# Keyboard__Schematic.net
KiCad netlist of a schematic drawn in EAGLE
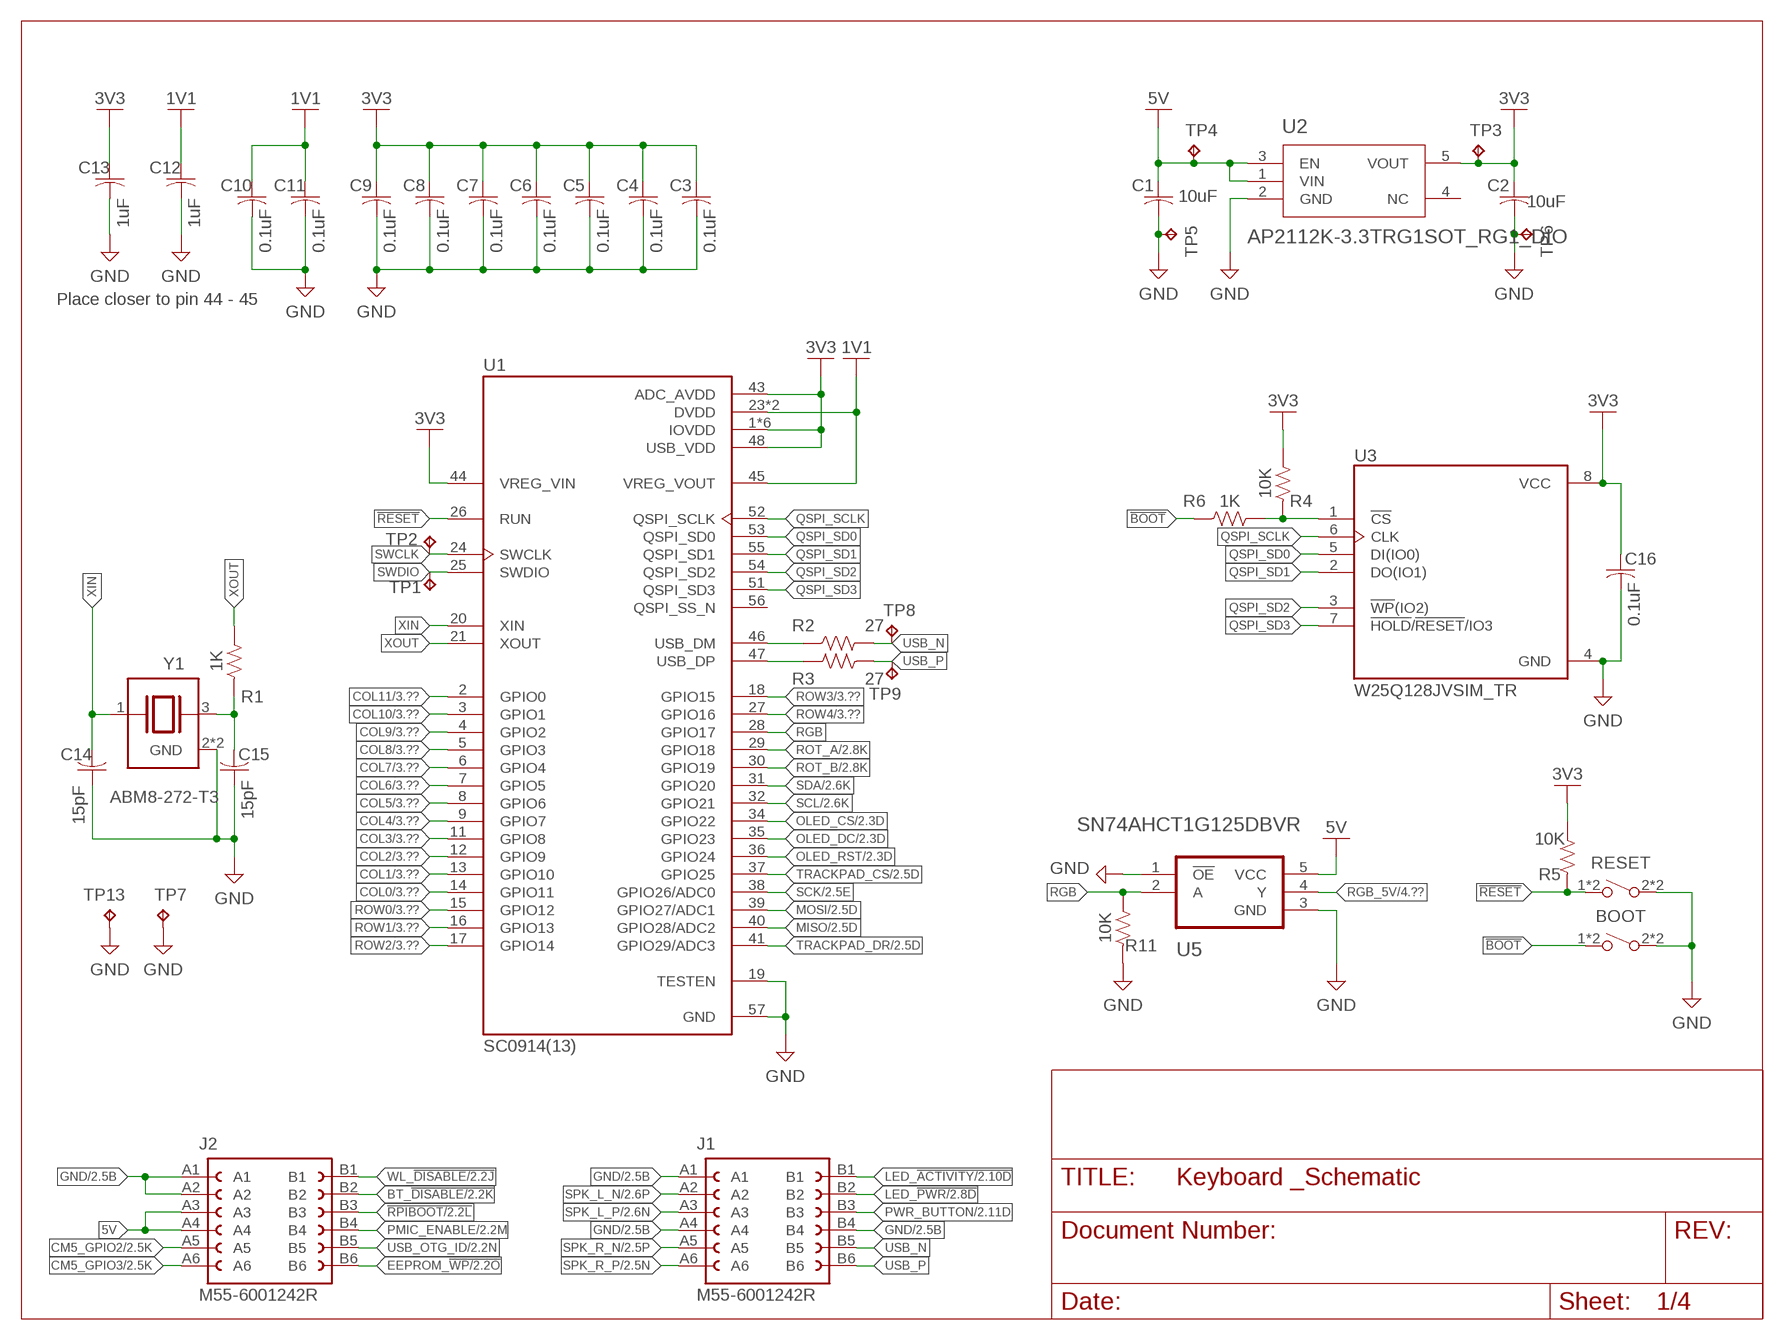
[diagram p0: schematic, sheet 1]
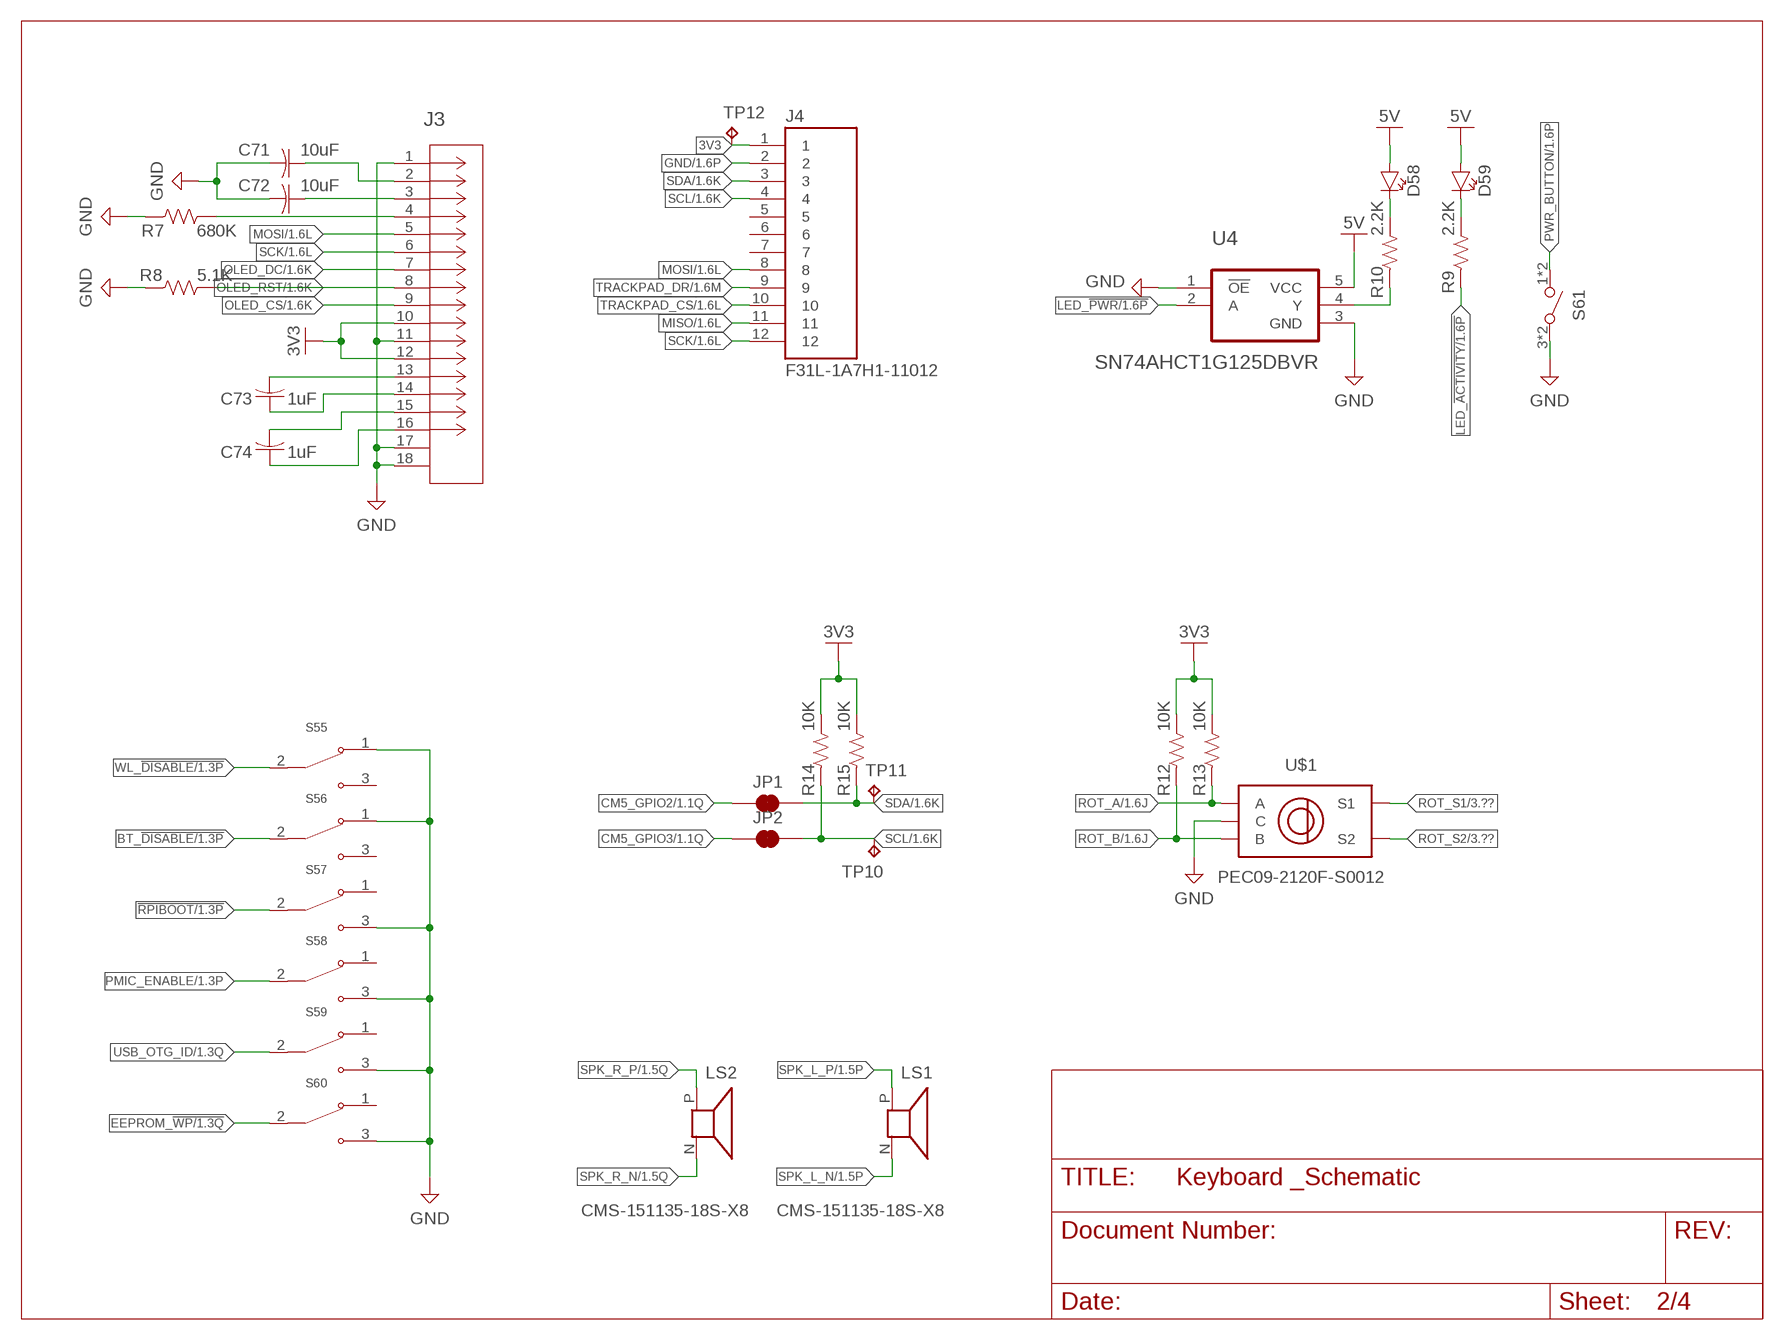
[diagram p1: schematic, sheet 2]
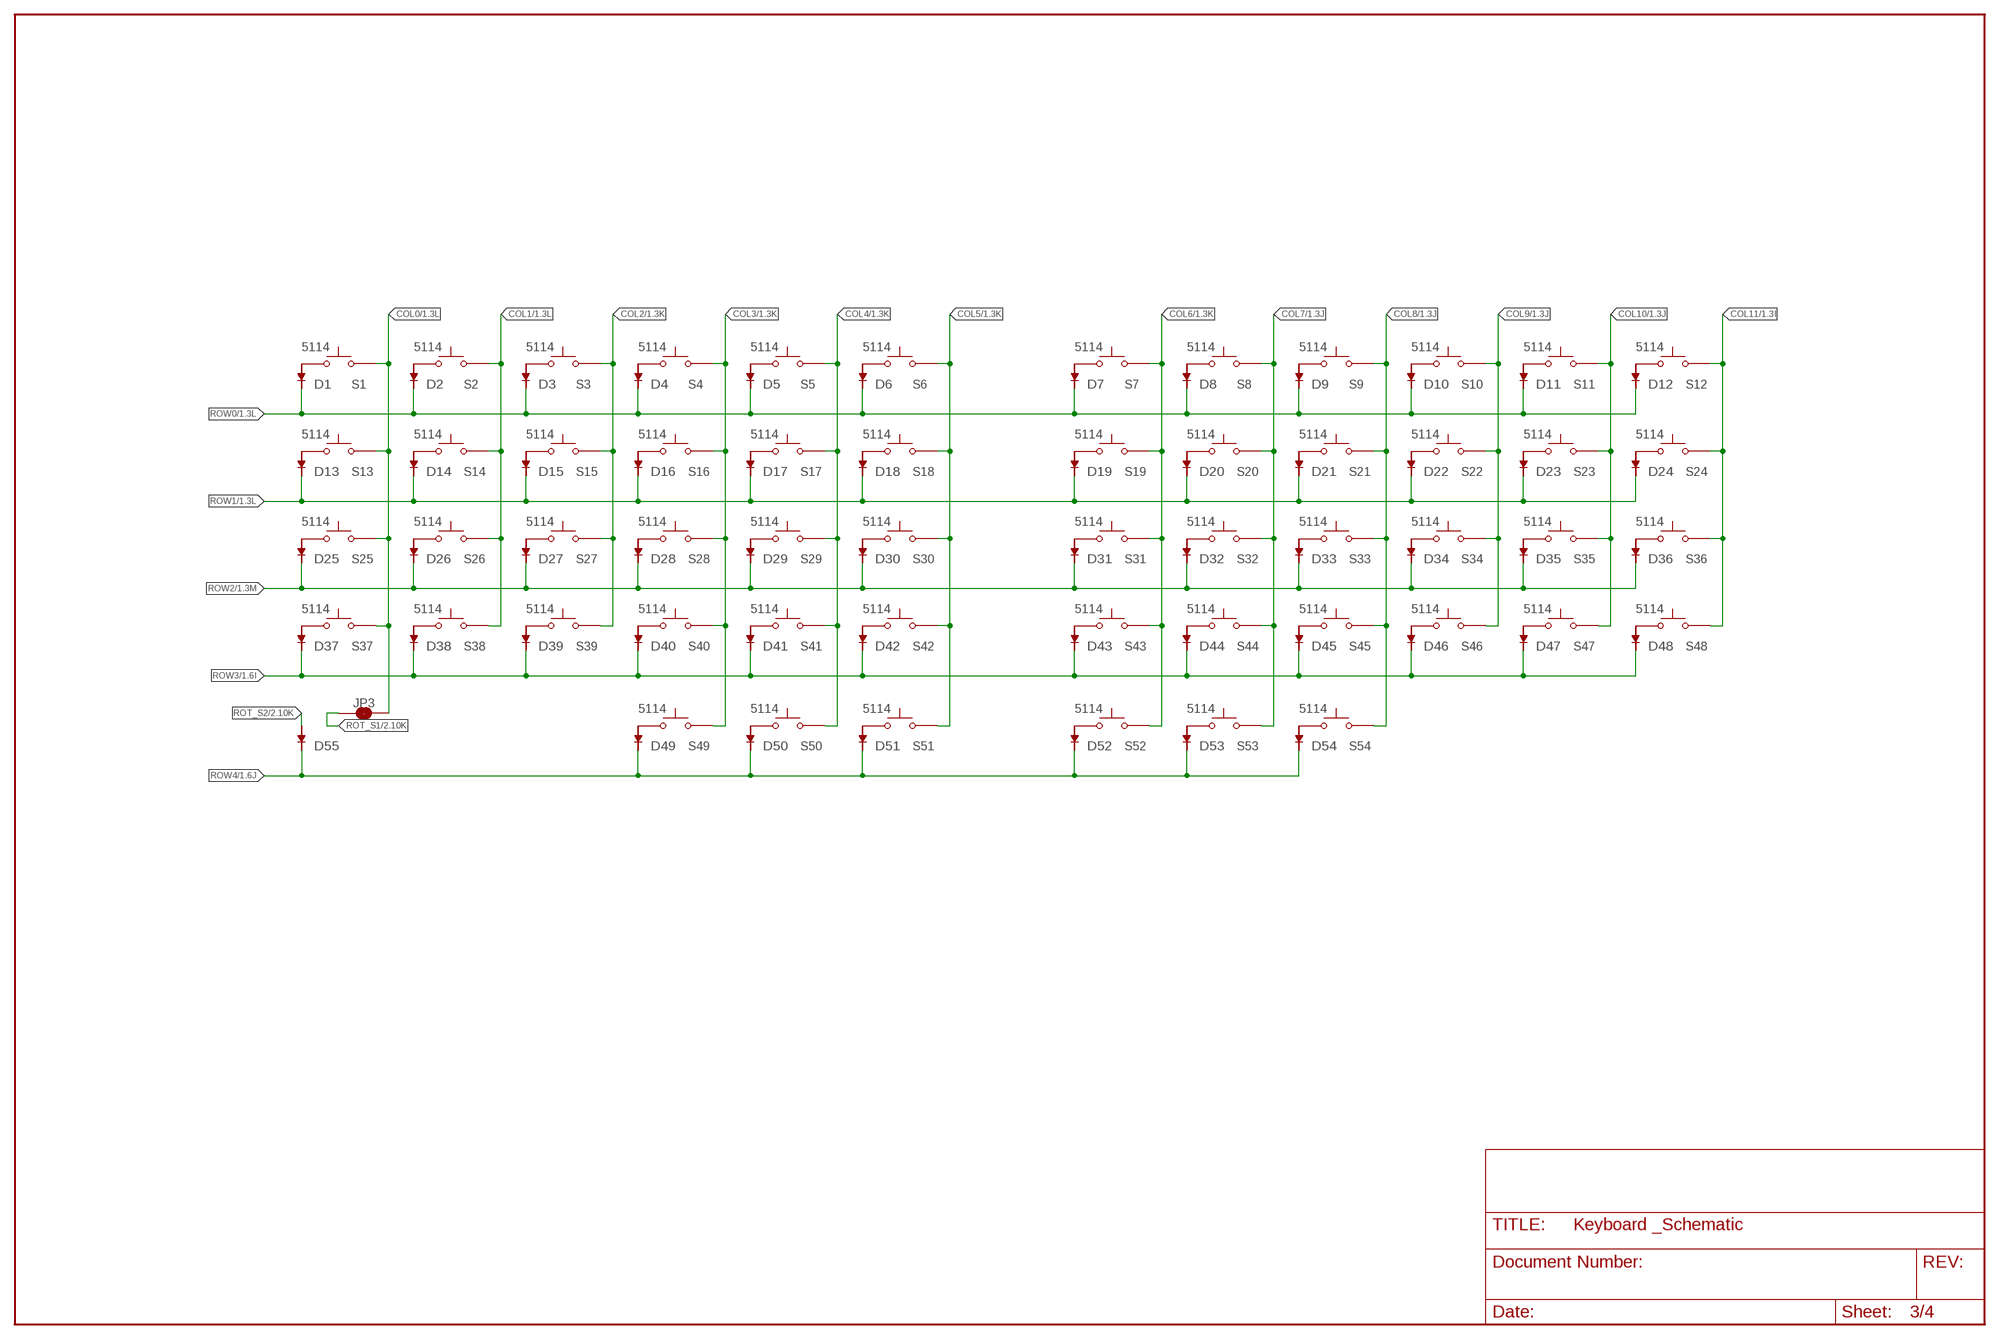
[diagram p2: schematic, sheet 3]
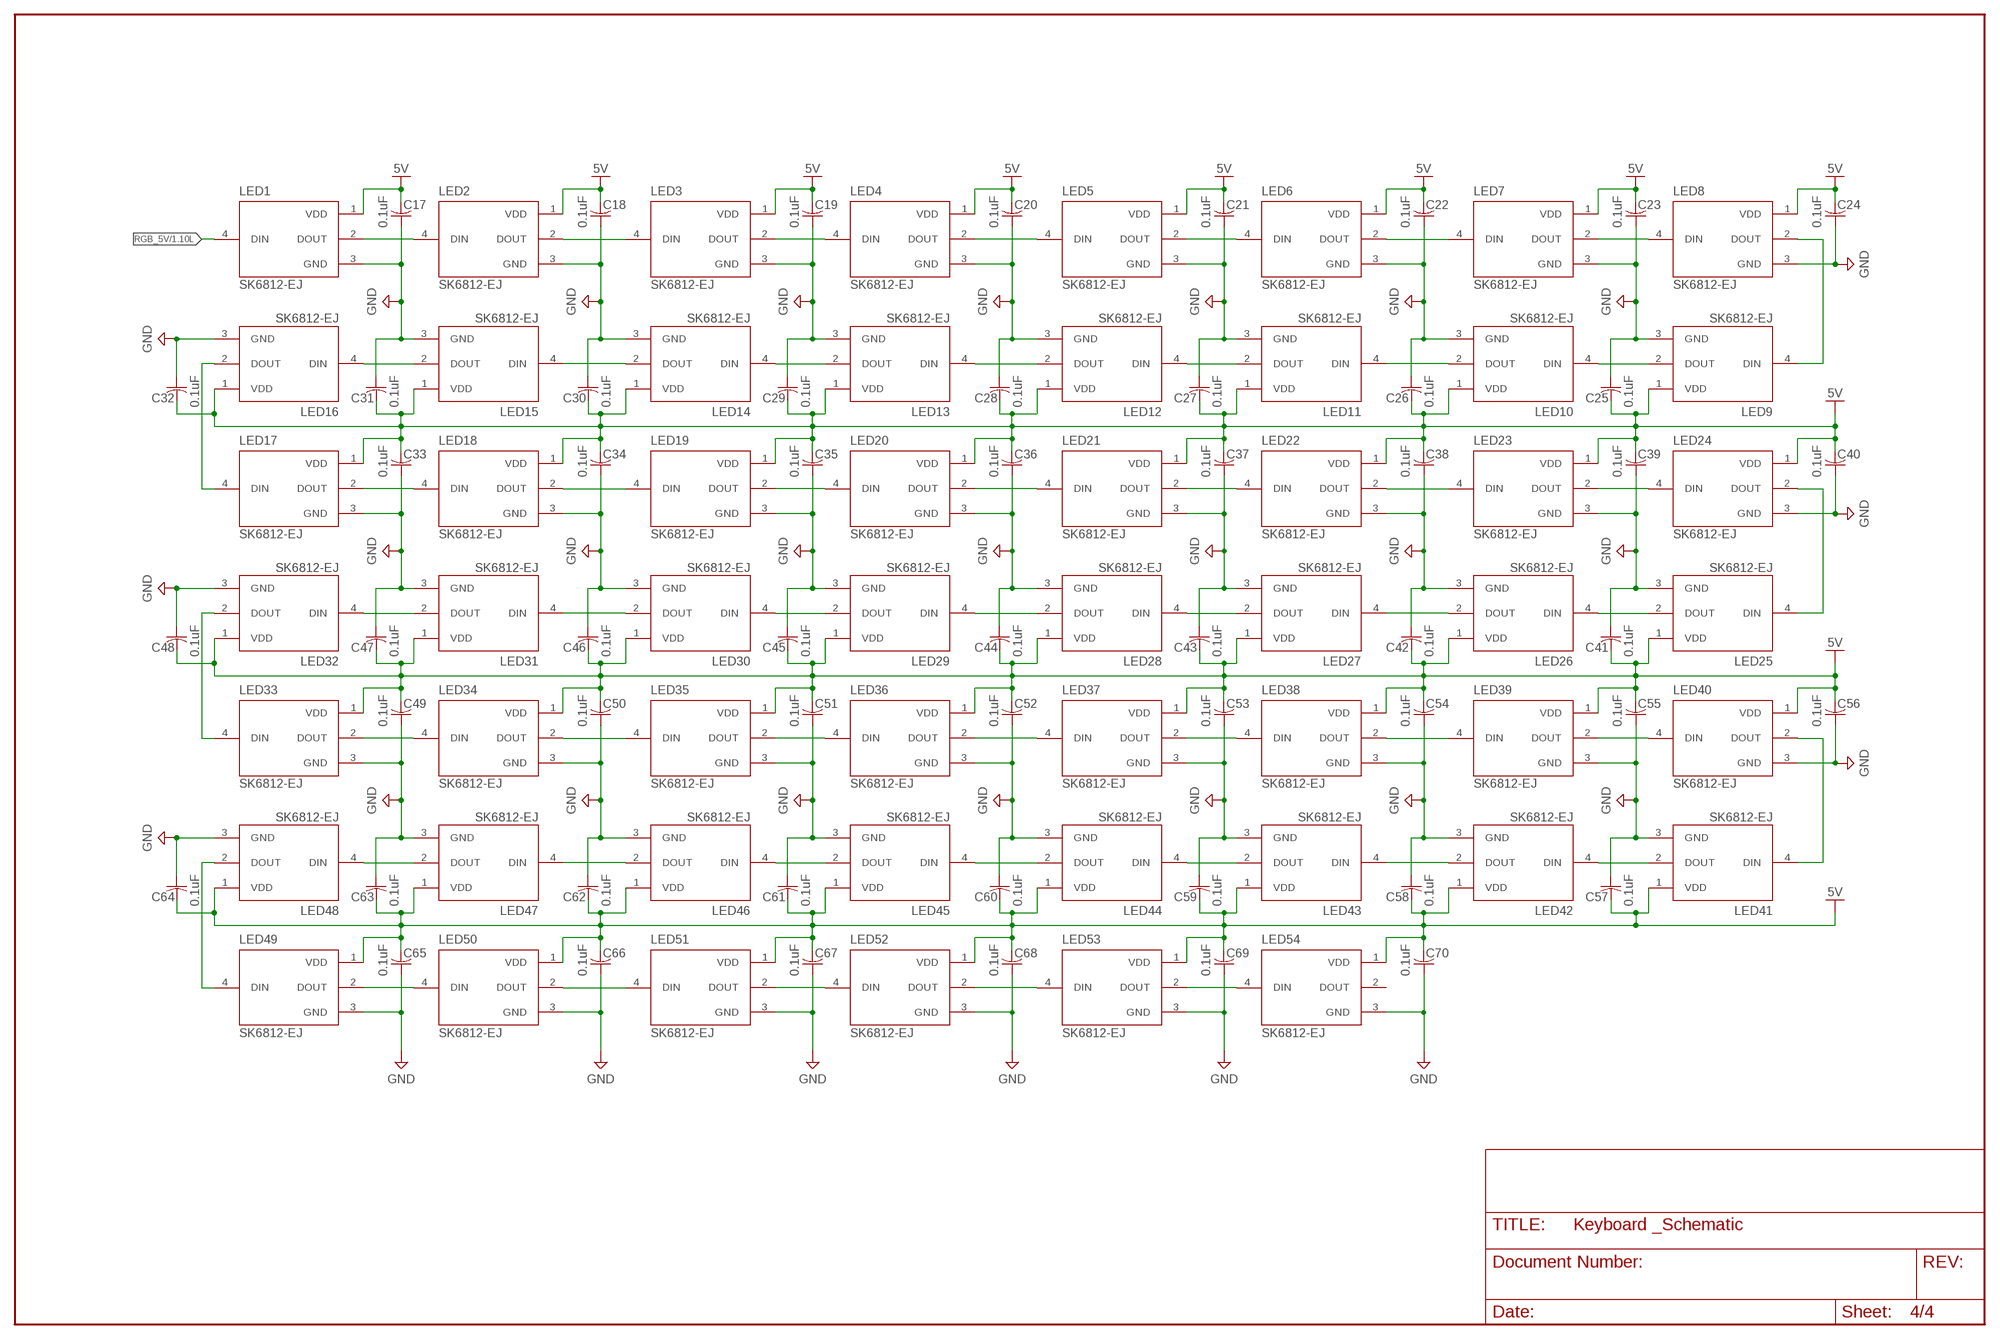
[diagram p3: schematic, sheet 4]

(export (version "E")
  (design (tool "Eeschema 10.0.6"))
  (components
    (comp (ref "BOOT")
      (value "SPST-NO_SWITCH_KMR2")
      (footprint "eagle-import:KMR2")
      (fields (field (name "MANUFACTURER") "C&K") (field (name "MPN") "KMR211G LFS"))
      (libsource (lib "eagle-import") (part "SPST-NO_SWITCH_KMR2"))
    )
    (comp (ref "C1")
      (value "10uF")
      (footprint "eagle-import:CAPC3216X135")
      (libsource (lib "eagle-import") (part "C-USCHIP-1206(3216-METRIC)_"))
    )
    (comp (ref "C2")
      (value "10uF")
      (footprint "eagle-import:CAPC3216X135")
      (libsource (lib "eagle-import") (part "C-USCHIP-1206(3216-METRIC)_"))
    )
    (comp (ref "C3")
      (value "0.1uF")
      (footprint "eagle-import:CAPC2012X110")
      (libsource (lib "eagle-import") (part "C-USCHIP-0805(2012-METRIC)_"))
    )
    (comp (ref "C4")
      (value "0.1uF")
      (footprint "eagle-import:CAPC2012X110")
      (libsource (lib "eagle-import") (part "C-USCHIP-0805(2012-METRIC)_"))
    )
    (comp (ref "C5")
      (value "0.1uF")
      (footprint "eagle-import:CAPC2012X110")
      (libsource (lib "eagle-import") (part "C-USCHIP-0805(2012-METRIC)_"))
    )
    (comp (ref "C6")
      (value "0.1uF")
      (footprint "eagle-import:CAPC2012X110")
      (libsource (lib "eagle-import") (part "C-USCHIP-0805(2012-METRIC)_"))
    )
    (comp (ref "C7")
      (value "0.1uF")
      (footprint "eagle-import:CAPC2012X110")
      (libsource (lib "eagle-import") (part "C-USCHIP-0805(2012-METRIC)_"))
    )
    (comp (ref "C8")
      (value "0.1uF")
      (footprint "eagle-import:CAPC2012X110")
      (libsource (lib "eagle-import") (part "C-USCHIP-0805(2012-METRIC)_"))
    )
    (comp (ref "C9")
      (value "0.1uF")
      (footprint "eagle-import:CAPC2012X110")
      (libsource (lib "eagle-import") (part "C-USCHIP-0805(2012-METRIC)_"))
    )
    (comp (ref "C10")
      (value "0.1uF")
      (footprint "eagle-import:CAPC2012X110")
      (libsource (lib "eagle-import") (part "C-USCHIP-0805(2012-METRIC)_"))
    )
    (comp (ref "C11")
      (value "0.1uF")
      (footprint "eagle-import:CAPC2012X110")
      (libsource (lib "eagle-import") (part "C-USCHIP-0805(2012-METRIC)_"))
    )
    (comp (ref "C12")
      (value "1uF")
      (footprint "eagle-import:CAPC2012X110")
      (libsource (lib "eagle-import") (part "C-USCHIP-0805(2012-METRIC)_"))
    )
    (comp (ref "C13")
      (value "1uF")
      (footprint "eagle-import:CAPC2012X110")
      (libsource (lib "eagle-import") (part "C-USCHIP-0805(2012-METRIC)_"))
    )
    (comp (ref "C14")
      (value "15pF")
      (footprint "eagle-import:CAPC2012X110")
      (libsource (lib "eagle-import") (part "C-USCHIP-0805(2012-METRIC)_"))
    )
    (comp (ref "C15")
      (value "15pF")
      (footprint "eagle-import:CAPC2012X110")
      (libsource (lib "eagle-import") (part "C-USCHIP-0805(2012-METRIC)_"))
    )
    (comp (ref "C16")
      (value "0.1uF")
      (footprint "eagle-import:CAPC2012X110")
      (libsource (lib "eagle-import") (part "C-USCHIP-0805(2012-METRIC)_"))
    )
    (comp (ref "J1")
      (value "M55-6001242R")
      (footprint "eagle-import:HARWIN_M55-6001242R")
      (fields (field (name "MANUFACTURER") "Harwin"))
      (libsource (lib "eagle-import") (part "M55-6001242R"))
    )
    (comp (ref "J2")
      (value "M55-6001242R")
      (footprint "eagle-import:HARWIN_M55-6001242R")
      (fields (field (name "MANUFACTURER") "Harwin"))
      (libsource (lib "eagle-import") (part "M55-6001242R"))
    )
    (comp (ref "R1")
      (value "1K")
      (footprint "eagle-import:RESC2012X65")
      (libsource (lib "eagle-import") (part "R-USCHIP-0805(2012-METRIC)_"))
    )
    (comp (ref "R2")
      (value "27")
      (footprint "eagle-import:RESC2012X65")
      (libsource (lib "eagle-import") (part "R-USCHIP-0805(2012-METRIC)_"))
    )
    (comp (ref "R3")
      (value "27")
      (footprint "eagle-import:RESC2012X65")
      (libsource (lib "eagle-import") (part "R-USCHIP-0805(2012-METRIC)_"))
    )
    (comp (ref "R4")
      (value "10K")
      (footprint "eagle-import:RESC2012X65")
      (libsource (lib "eagle-import") (part "R-USCHIP-0805(2012-METRIC)_"))
    )
    (comp (ref "R5")
      (value "10K")
      (footprint "eagle-import:RESC2012X65")
      (libsource (lib "eagle-import") (part "R-USCHIP-0805(2012-METRIC)_"))
    )
    (comp (ref "R6")
      (value "1K")
      (footprint "eagle-import:RESC2012X65")
      (libsource (lib "eagle-import") (part "R-USCHIP-0805(2012-METRIC)_"))
    )
    (comp (ref "R11")
      (value "10K")
      (footprint "eagle-import:RESC2012X65")
      (libsource (lib "eagle-import") (part "R-USCHIP-0805(2012-METRIC)_"))
    )
    (comp (ref "RESET")
      (value "SPST-NO_SWITCH_KMR2")
      (footprint "eagle-import:KMR2")
      (fields (field (name "MANUFACTURER") "C&K") (field (name "MPN") "KMR211G LFS"))
      (libsource (lib "eagle-import") (part "SPST-NO_SWITCH_KMR2"))
    )
    (comp (ref "TP1")
      (value "TPB2,54")
      (footprint "eagle-import:B2,54")
      (libsource (lib "eagle-import") (part "TPB2,54"))
    )
    (comp (ref "TP2")
      (value "TPB2,54")
      (footprint "eagle-import:B2,54")
      (libsource (lib "eagle-import") (part "TPB2,54"))
    )
    (comp (ref "TP3")
      (value "TPB2,54")
      (footprint "eagle-import:B2,54")
      (libsource (lib "eagle-import") (part "TPB2,54"))
    )
    (comp (ref "TP4")
      (value "TPB1,27")
      (footprint "eagle-import:B1,27")
      (libsource (lib "eagle-import") (part "TPB1,27"))
    )
    (comp (ref "TP5")
      (value "TPB2,54")
      (footprint "eagle-import:B2,54")
      (libsource (lib "eagle-import") (part "TPB2,54"))
    )
    (comp (ref "TP6")
      (value "TPB1,27")
      (footprint "eagle-import:B1,27")
      (libsource (lib "eagle-import") (part "TPB1,27"))
    )
    (comp (ref "TP7")
      (value "TPB1,27")
      (footprint "eagle-import:B1,27")
      (libsource (lib "eagle-import") (part "TPB1,27"))
    )
    (comp (ref "TP8")
      (value "TPB1,27")
      (footprint "eagle-import:B1,27")
      (libsource (lib "eagle-import") (part "TPB1,27"))
    )
    (comp (ref "TP9")
      (value "TPB1,27")
      (footprint "eagle-import:B1,27")
      (libsource (lib "eagle-import") (part "TPB1,27"))
    )
    (comp (ref "TP13")
      (value "TPB2,54")
      (footprint "eagle-import:B2,54")
      (libsource (lib "eagle-import") (part "TPB2,54"))
    )
    (comp (ref "U1")
      (value "SC0914(13)")
      (footprint "eagle-import:QFN40P700X700X90-57N")
      (fields (field (name "MANUFACTURER") "Raspberry Pi"))
      (libsource (lib "eagle-import") (part "SC0914(13)"))
    )
    (comp (ref "U2")
      (value "AP2112K-3.3TRG1SOT_RG1_DIO")
      (footprint "eagle-import:SOT_RG1_DIO")
      (fields
        (field (name "MANUFACTURER_PART_NUMBER") "AP2112K-3.3TRG1")
        (field (name "COPYRIGHT") "Copyright (C) 2025 Ultra Librarian. All rights reserved.")
      )
      (libsource (lib "eagle-import") (part "AP2112K-3.3TRG1SOT_RG1_DIO"))
    )
    (comp (ref "U3")
      (value "W25Q128JVSIM_TR")
      (footprint "eagle-import:SOIC127P790X216-8N")
      (fields (field (name "MF") "Winbond Electronics") (field (name "MP") "W25Q128JVSIM TR"))
      (libsource (lib "eagle-import") (part "W25Q128JVSIM_TR"))
    )
    (comp (ref "U5")
      (value "SN74AHCT1G125DBVR")
      (footprint "eagle-import:SOT95P280X145-5N")
      (libsource (lib "eagle-import") (part "SN74AHCT1G125DBVR"))
    )
    (comp (ref "Y1")
      (value "ABM8-272-T3")
      (footprint "eagle-import:XTAL_ABM8-272-T3")
      (fields (field (name "MANUFACTURER") "ABRACON") (field (name "CREATOR") "DIZAR"))
      (libsource (lib "eagle-import") (part "ABM8-272-T3"))
    )
    (comp (ref "D1")
      (value "1N4148W")
      (footprint "eagle-import:SOD3715X135N")
      (fields (field (name "MF") "Diodes Inc.") (field (name "MP") "1N4148W-7-F"))
      (libsource (lib "eagle-import") (part "1N4148W"))
    )
    (comp (ref "D2")
      (value "1N4148W")
      (footprint "eagle-import:SOD3715X135N")
      (fields (field (name "MF") "Diodes Inc.") (field (name "MP") "1N4148W-7-F"))
      (libsource (lib "eagle-import") (part "1N4148W"))
    )
    (comp (ref "D3")
      (value "1N4148W")
      (footprint "eagle-import:SOD3715X135N")
      (fields (field (name "MF") "Diodes Inc.") (field (name "MP") "1N4148W-7-F"))
      (libsource (lib "eagle-import") (part "1N4148W"))
    )
    (comp (ref "D4")
      (value "1N4148W")
      (footprint "eagle-import:SOD3715X135N")
      (fields (field (name "MF") "Diodes Inc.") (field (name "MP") "1N4148W-7-F"))
      (libsource (lib "eagle-import") (part "1N4148W"))
    )
    (comp (ref "D5")
      (value "1N4148W")
      (footprint "eagle-import:SOD3715X135N")
      (fields (field (name "MF") "Diodes Inc.") (field (name "MP") "1N4148W-7-F"))
      (libsource (lib "eagle-import") (part "1N4148W"))
    )
    (comp (ref "D6")
      (value "1N4148W")
      (footprint "eagle-import:SOD3715X135N")
      (fields (field (name "MF") "Diodes Inc.") (field (name "MP") "1N4148W-7-F"))
      (libsource (lib "eagle-import") (part "1N4148W"))
    )
    (comp (ref "D7")
      (value "1N4148W")
      (footprint "eagle-import:SOD3715X135N")
      (fields (field (name "MF") "Diodes Inc.") (field (name "MP") "1N4148W-7-F"))
      (libsource (lib "eagle-import") (part "1N4148W"))
    )
    (comp (ref "D8")
      (value "1N4148W")
      (footprint "eagle-import:SOD3715X135N")
      (fields (field (name "MF") "Diodes Inc.") (field (name "MP") "1N4148W-7-F"))
      (libsource (lib "eagle-import") (part "1N4148W"))
    )
    (comp (ref "D9")
      (value "1N4148W")
      (footprint "eagle-import:SOD3715X135N")
      (fields (field (name "MF") "Diodes Inc.") (field (name "MP") "1N4148W-7-F"))
      (libsource (lib "eagle-import") (part "1N4148W"))
    )
    (comp (ref "D10")
      (value "1N4148W")
      (footprint "eagle-import:SOD3715X135N")
      (fields (field (name "MF") "Diodes Inc.") (field (name "MP") "1N4148W-7-F"))
      (libsource (lib "eagle-import") (part "1N4148W"))
    )
    (comp (ref "D11")
      (value "1N4148W")
      (footprint "eagle-import:SOD3715X135N")
      (fields (field (name "MF") "Diodes Inc.") (field (name "MP") "1N4148W-7-F"))
      (libsource (lib "eagle-import") (part "1N4148W"))
    )
    (comp (ref "D12")
      (value "1N4148W")
      (footprint "eagle-import:SOD3715X135N")
      (fields (field (name "MF") "Diodes Inc.") (field (name "MP") "1N4148W-7-F"))
      (libsource (lib "eagle-import") (part "1N4148W"))
    )
    (comp (ref "D13")
      (value "1N4148W")
      (footprint "eagle-import:SOD3715X135N")
      (fields (field (name "MF") "Diodes Inc.") (field (name "MP") "1N4148W-7-F"))
      (libsource (lib "eagle-import") (part "1N4148W"))
    )
    (comp (ref "D14")
      (value "1N4148W")
      (footprint "eagle-import:SOD3715X135N")
      (fields (field (name "MF") "Diodes Inc.") (field (name "MP") "1N4148W-7-F"))
      (libsource (lib "eagle-import") (part "1N4148W"))
    )
    (comp (ref "D15")
      (value "1N4148W")
      (footprint "eagle-import:SOD3715X135N")
      (fields (field (name "MF") "Diodes Inc.") (field (name "MP") "1N4148W-7-F"))
      (libsource (lib "eagle-import") (part "1N4148W"))
    )
    (comp (ref "D16")
      (value "1N4148W")
      (footprint "eagle-import:SOD3715X135N")
      (fields (field (name "MF") "Diodes Inc.") (field (name "MP") "1N4148W-7-F"))
      (libsource (lib "eagle-import") (part "1N4148W"))
    )
    (comp (ref "D17")
      (value "1N4148W")
      (footprint "eagle-import:SOD3715X135N")
      (fields (field (name "MF") "Diodes Inc.") (field (name "MP") "1N4148W-7-F"))
      (libsource (lib "eagle-import") (part "1N4148W"))
    )
    (comp (ref "D18")
      (value "1N4148W")
      (footprint "eagle-import:SOD3715X135N")
      (fields (field (name "MF") "Diodes Inc.") (field (name "MP") "1N4148W-7-F"))
      (libsource (lib "eagle-import") (part "1N4148W"))
    )
    (comp (ref "D19")
      (value "1N4148W")
      (footprint "eagle-import:SOD3715X135N")
      (fields (field (name "MF") "Diodes Inc.") (field (name "MP") "1N4148W-7-F"))
      (libsource (lib "eagle-import") (part "1N4148W"))
    )
    (comp (ref "D20")
      (value "1N4148W")
      (footprint "eagle-import:SOD3715X135N")
      (fields (field (name "MF") "Diodes Inc.") (field (name "MP") "1N4148W-7-F"))
      (libsource (lib "eagle-import") (part "1N4148W"))
    )
    (comp (ref "D21")
      (value "1N4148W")
      (footprint "eagle-import:SOD3715X135N")
      (fields (field (name "MF") "Diodes Inc.") (field (name "MP") "1N4148W-7-F"))
      (libsource (lib "eagle-import") (part "1N4148W"))
    )
    (comp (ref "D22")
      (value "1N4148W")
      (footprint "eagle-import:SOD3715X135N")
      (fields (field (name "MF") "Diodes Inc.") (field (name "MP") "1N4148W-7-F"))
      (libsource (lib "eagle-import") (part "1N4148W"))
    )
    (comp (ref "D23")
      (value "1N4148W")
      (footprint "eagle-import:SOD3715X135N")
      (fields (field (name "MF") "Diodes Inc.") (field (name "MP") "1N4148W-7-F"))
      (libsource (lib "eagle-import") (part "1N4148W"))
    )
    (comp (ref "D24")
      (value "1N4148W")
      (footprint "eagle-import:SOD3715X135N")
      (fields (field (name "MF") "Diodes Inc.") (field (name "MP") "1N4148W-7-F"))
      (libsource (lib "eagle-import") (part "1N4148W"))
    )
    (comp (ref "D25")
      (value "1N4148W")
      (footprint "eagle-import:SOD3715X135N")
      (fields (field (name "MF") "Diodes Inc.") (field (name "MP") "1N4148W-7-F"))
      (libsource (lib "eagle-import") (part "1N4148W"))
    )
    (comp (ref "D26")
      (value "1N4148W")
      (footprint "eagle-import:SOD3715X135N")
      (fields (field (name "MF") "Diodes Inc.") (field (name "MP") "1N4148W-7-F"))
      (libsource (lib "eagle-import") (part "1N4148W"))
    )
    (comp (ref "D27")
      (value "1N4148W")
      (footprint "eagle-import:SOD3715X135N")
      (fields (field (name "MF") "Diodes Inc.") (field (name "MP") "1N4148W-7-F"))
      (libsource (lib "eagle-import") (part "1N4148W"))
    )
    (comp (ref "D28")
      (value "1N4148W")
      (footprint "eagle-import:SOD3715X135N")
      (fields (field (name "MF") "Diodes Inc.") (field (name "MP") "1N4148W-7-F"))
      (libsource (lib "eagle-import") (part "1N4148W"))
    )
    (comp (ref "D29")
      (value "1N4148W")
      (footprint "eagle-import:SOD3715X135N")
      (fields (field (name "MF") "Diodes Inc.") (field (name "MP") "1N4148W-7-F"))
      (libsource (lib "eagle-import") (part "1N4148W"))
    )
    (comp (ref "D30")
      (value "1N4148W")
      (footprint "eagle-import:SOD3715X135N")
      (fields (field (name "MF") "Diodes Inc.") (field (name "MP") "1N4148W-7-F"))
      (libsource (lib "eagle-import") (part "1N4148W"))
    )
    (comp (ref "D31")
      (value "1N4148W")
      (footprint "eagle-import:SOD3715X135N")
      (fields (field (name "MF") "Diodes Inc.") (field (name "MP") "1N4148W-7-F"))
      (libsource (lib "eagle-import") (part "1N4148W"))
    )
    (comp (ref "D32")
      (value "1N4148W")
      (footprint "eagle-import:SOD3715X135N")
      (fields (field (name "MF") "Diodes Inc.") (field (name "MP") "1N4148W-7-F"))
      (libsource (lib "eagle-import") (part "1N4148W"))
    )
    (comp (ref "D33")
      (value "1N4148W")
      (footprint "eagle-import:SOD3715X135N")
      (fields (field (name "MF") "Diodes Inc.") (field (name "MP") "1N4148W-7-F"))
      (libsource (lib "eagle-import") (part "1N4148W"))
    )
    (comp (ref "D34")
      (value "1N4148W")
      (footprint "eagle-import:SOD3715X135N")
      (fields (field (name "MF") "Diodes Inc.") (field (name "MP") "1N4148W-7-F"))
      (libsource (lib "eagle-import") (part "1N4148W"))
    )
    (comp (ref "D35")
      (value "1N4148W")
      (footprint "eagle-import:SOD3715X135N")
      (fields (field (name "MF") "Diodes Inc.") (field (name "MP") "1N4148W-7-F"))
      (libsource (lib "eagle-import") (part "1N4148W"))
    )
    (comp (ref "D36")
      (value "1N4148W")
      (footprint "eagle-import:SOD3715X135N")
      (fields (field (name "MF") "Diodes Inc.") (field (name "MP") "1N4148W-7-F"))
      (libsource (lib "eagle-import") (part "1N4148W"))
    )
    (comp (ref "D37")
      (value "1N4148W")
      (footprint "eagle-import:SOD3715X135N")
      (fields (field (name "MF") "Diodes Inc.") (field (name "MP") "1N4148W-7-F"))
      (libsource (lib "eagle-import") (part "1N4148W"))
    )
    (comp (ref "D38")
      (value "1N4148W")
      (footprint "eagle-import:SOD3715X135N")
      (fields (field (name "MF") "Diodes Inc.") (field (name "MP") "1N4148W-7-F"))
      (libsource (lib "eagle-import") (part "1N4148W"))
    )
    (comp (ref "D39")
      (value "1N4148W")
      (footprint "eagle-import:SOD3715X135N")
      (fields (field (name "MF") "Diodes Inc.") (field (name "MP") "1N4148W-7-F"))
      (libsource (lib "eagle-import") (part "1N4148W"))
    )
    (comp (ref "D40")
      (value "1N4148W")
      (footprint "eagle-import:SOD3715X135N")
      (fields (field (name "MF") "Diodes Inc.") (field (name "MP") "1N4148W-7-F"))
      (libsource (lib "eagle-import") (part "1N4148W"))
    )
    (comp (ref "D41")
      (value "1N4148W")
      (footprint "eagle-import:SOD3715X135N")
      (fields (field (name "MF") "Diodes Inc.") (field (name "MP") "1N4148W-7-F"))
      (libsource (lib "eagle-import") (part "1N4148W"))
    )
    (comp (ref "D42")
      (value "1N4148W")
      (footprint "eagle-import:SOD3715X135N")
      (fields (field (name "MF") "Diodes Inc.") (field (name "MP") "1N4148W-7-F"))
      (libsource (lib "eagle-import") (part "1N4148W"))
    )
    (comp (ref "D43")
      (value "1N4148W")
      (footprint "eagle-import:SOD3715X135N")
      (fields (field (name "MF") "Diodes Inc.") (field (name "MP") "1N4148W-7-F"))
      (libsource (lib "eagle-import") (part "1N4148W"))
    )
    (comp (ref "D44")
      (value "1N4148W")
      (footprint "eagle-import:SOD3715X135N")
      (fields (field (name "MF") "Diodes Inc.") (field (name "MP") "1N4148W-7-F"))
      (libsource (lib "eagle-import") (part "1N4148W"))
    )
    (comp (ref "D45")
      (value "1N4148W")
      (footprint "eagle-import:SOD3715X135N")
      (fields (field (name "MF") "Diodes Inc.") (field (name "MP") "1N4148W-7-F"))
      (libsource (lib "eagle-import") (part "1N4148W"))
    )
    (comp (ref "D46")
      (value "1N4148W")
      (footprint "eagle-import:SOD3715X135N")
      (fields (field (name "MF") "Diodes Inc.") (field (name "MP") "1N4148W-7-F"))
      (libsource (lib "eagle-import") (part "1N4148W"))
    )
    (comp (ref "D47")
      (value "1N4148W")
      (footprint "eagle-import:SOD3715X135N")
      (fields (field (name "MF") "Diodes Inc.") (field (name "MP") "1N4148W-7-F"))
      (libsource (lib "eagle-import") (part "1N4148W"))
    )
    (comp (ref "D48")
      (value "1N4148W")
      (footprint "eagle-import:SOD3715X135N")
      (fields (field (name "MF") "Diodes Inc.") (field (name "MP") "1N4148W-7-F"))
      (libsource (lib "eagle-import") (part "1N4148W"))
    )
    (comp (ref "D49")
      (value "1N4148W")
      (footprint "eagle-import:SOD3715X135N")
      (fields (field (name "MF") "Diodes Inc.") (field (name "MP") "1N4148W-7-F"))
      (libsource (lib "eagle-import") (part "1N4148W"))
    )
    (comp (ref "D50")
      (value "1N4148W")
      (footprint "eagle-import:SOD3715X135N")
      (fields (field (name "MF") "Diodes Inc.") (field (name "MP") "1N4148W-7-F"))
      (libsource (lib "eagle-import") (part "1N4148W"))
    )
    (comp (ref "D51")
      (value "1N4148W")
      (footprint "eagle-import:SOD3715X135N")
      (fields (field (name "MF") "Diodes Inc.") (field (name "MP") "1N4148W-7-F"))
      (libsource (lib "eagle-import") (part "1N4148W"))
    )
    (comp (ref "D52")
      (value "1N4148W")
      (footprint "eagle-import:SOD3715X135N")
      (fields (field (name "MF") "Diodes Inc.") (field (name "MP") "1N4148W-7-F"))
      (libsource (lib "eagle-import") (part "1N4148W"))
    )
    (comp (ref "D53")
      (value "1N4148W")
      (footprint "eagle-import:SOD3715X135N")
      (fields (field (name "MF") "Diodes Inc.") (field (name "MP") "1N4148W-7-F"))
      (libsource (lib "eagle-import") (part "1N4148W"))
    )
    (comp (ref "D54")
      (value "1N4148W")
      (footprint "eagle-import:SOD3715X135N")
      (fields (field (name "MF") "Diodes Inc.") (field (name "MP") "1N4148W-7-F"))
      (libsource (lib "eagle-import") (part "1N4148W"))
    )
    (comp (ref "D55")
      (value "1N4148W")
      (footprint "eagle-import:SOD3715X135N")
      (fields (field (name "MF") "Diodes Inc.") (field (name "MP") "1N4148W-7-F"))
      (libsource (lib "eagle-import") (part "1N4148W"))
    )
    (comp (ref "JP3")
      (value "JUMPER-SMT_2_NC_TRACE_NO-SILK")
      (footprint "eagle-import:SMT-JUMPER_2_NC_TRACE_NO-SILK")
      (libsource (lib "eagle-import") (part "JUMPER-SMT_2_NC_TRACE_NO-SILK"))
    )
    (comp (ref "S1")
      (value "5114")
      (footprint "eagle-import:SW_5114")
      (fields (field (name "MF") "Adafruit Industries LLC"))
      (libsource (lib "eagle-import") (part "5114"))
    )
    (comp (ref "S2")
      (value "5114")
      (footprint "eagle-import:SW_5114")
      (fields (field (name "MF") "Adafruit Industries LLC"))
      (libsource (lib "eagle-import") (part "5114"))
    )
    (comp (ref "S3")
      (value "5114")
      (footprint "eagle-import:SW_5114")
      (fields (field (name "MF") "Adafruit Industries LLC"))
      (libsource (lib "eagle-import") (part "5114"))
    )
    (comp (ref "S4")
      (value "5114")
      (footprint "eagle-import:SW_5114")
      (fields (field (name "MF") "Adafruit Industries LLC"))
      (libsource (lib "eagle-import") (part "5114"))
    )
    (comp (ref "S5")
      (value "5114")
      (footprint "eagle-import:SW_5114")
      (fields (field (name "MF") "Adafruit Industries LLC"))
      (libsource (lib "eagle-import") (part "5114"))
    )
    (comp (ref "S6")
      (value "5114")
      (footprint "eagle-import:SW_5114")
      (fields (field (name "MF") "Adafruit Industries LLC"))
      (libsource (lib "eagle-import") (part "5114"))
    )
    (comp (ref "S7")
      (value "5114")
      (footprint "eagle-import:SW_5114")
      (fields (field (name "MF") "Adafruit Industries LLC"))
      (libsource (lib "eagle-import") (part "5114"))
    )
    (comp (ref "S8")
      (value "5114")
      (footprint "eagle-import:SW_5114")
      (fields (field (name "MF") "Adafruit Industries LLC"))
      (libsource (lib "eagle-import") (part "5114"))
    )
    (comp (ref "S9")
      (value "5114")
      (footprint "eagle-import:SW_5114")
      (fields (field (name "MF") "Adafruit Industries LLC"))
      (libsource (lib "eagle-import") (part "5114"))
    )
    (comp (ref "S10")
      (value "5114")
      (footprint "eagle-import:SW_5114")
      (fields (field (name "MF") "Adafruit Industries LLC"))
      (libsource (lib "eagle-import") (part "5114"))
    )
    (comp (ref "S11")
      (value "5114")
      (footprint "eagle-import:SW_5114")
      (fields (field (name "MF") "Adafruit Industries LLC"))
      (libsource (lib "eagle-import") (part "5114"))
    )
    (comp (ref "S12")
      (value "5114")
      (footprint "eagle-import:SW_5114")
      (fields (field (name "MF") "Adafruit Industries LLC"))
      (libsource (lib "eagle-import") (part "5114"))
    )
    (comp (ref "S13")
      (value "5114")
      (footprint "eagle-import:SW_5114")
      (fields (field (name "MF") "Adafruit Industries LLC"))
      (libsource (lib "eagle-import") (part "5114"))
    )
    (comp (ref "S14")
      (value "5114")
      (footprint "eagle-import:SW_5114")
      (fields (field (name "MF") "Adafruit Industries LLC"))
      (libsource (lib "eagle-import") (part "5114"))
    )
    (comp (ref "S15")
      (value "5114")
      (footprint "eagle-import:SW_5114")
      (fields (field (name "MF") "Adafruit Industries LLC"))
      (libsource (lib "eagle-import") (part "5114"))
    )
    (comp (ref "S16")
      (value "5114")
      (footprint "eagle-import:SW_5114")
      (fields (field (name "MF") "Adafruit Industries LLC"))
      (libsource (lib "eagle-import") (part "5114"))
    )
    (comp (ref "S17")
      (value "5114")
      (footprint "eagle-import:SW_5114")
      (fields (field (name "MF") "Adafruit Industries LLC"))
      (libsource (lib "eagle-import") (part "5114"))
    )
    (comp (ref "S18")
      (value "5114")
      (footprint "eagle-import:SW_5114")
      (fields (field (name "MF") "Adafruit Industries LLC"))
      (libsource (lib "eagle-import") (part "5114"))
    )
    (comp (ref "S19")
      (value "5114")
      (footprint "eagle-import:SW_5114")
      (fields (field (name "MF") "Adafruit Industries LLC"))
      (libsource (lib "eagle-import") (part "5114"))
    )
    (comp (ref "S20")
      (value "5114")
      (footprint "eagle-import:SW_5114")
      (fields (field (name "MF") "Adafruit Industries LLC"))
      (libsource (lib "eagle-import") (part "5114"))
    )
    (comp (ref "S21")
      (value "5114")
      (footprint "eagle-import:SW_5114")
      (fields (field (name "MF") "Adafruit Industries LLC"))
      (libsource (lib "eagle-import") (part "5114"))
    )
    (comp (ref "S22")
      (value "5114")
      (footprint "eagle-import:SW_5114")
      (fields (field (name "MF") "Adafruit Industries LLC"))
      (libsource (lib "eagle-import") (part "5114"))
    )
    (comp (ref "S23")
      (value "5114")
      (footprint "eagle-import:SW_5114")
      (fields (field (name "MF") "Adafruit Industries LLC"))
      (libsource (lib "eagle-import") (part "5114"))
    )
    (comp (ref "S24")
      (value "5114")
      (footprint "eagle-import:SW_5114")
      (fields (field (name "MF") "Adafruit Industries LLC"))
      (libsource (lib "eagle-import") (part "5114"))
    )
    (comp (ref "S25")
      (value "5114")
      (footprint "eagle-import:SW_5114")
      (fields (field (name "MF") "Adafruit Industries LLC"))
      (libsource (lib "eagle-import") (part "5114"))
    )
    (comp (ref "S26")
      (value "5114")
      (footprint "eagle-import:SW_5114")
      (fields (field (name "MF") "Adafruit Industries LLC"))
      (libsource (lib "eagle-import") (part "5114"))
    )
    (comp (ref "S27")
      (value "5114")
      (footprint "eagle-import:SW_5114")
      (fields (field (name "MF") "Adafruit Industries LLC"))
      (libsource (lib "eagle-import") (part "5114"))
    )
    (comp (ref "S28")
      (value "5114")
      (footprint "eagle-import:SW_5114")
      (fields (field (name "MF") "Adafruit Industries LLC"))
      (libsource (lib "eagle-import") (part "5114"))
    )
    (comp (ref "S29")
      (value "5114")
      (footprint "eagle-import:SW_5114")
      (fields (field (name "MF") "Adafruit Industries LLC"))
      (libsource (lib "eagle-import") (part "5114"))
    )
    (comp (ref "S30")
      (value "5114")
      (footprint "eagle-import:SW_5114")
      (fields (field (name "MF") "Adafruit Industries LLC"))
      (libsource (lib "eagle-import") (part "5114"))
    )
    (comp (ref "S31")
      (value "5114")
      (footprint "eagle-import:SW_5114")
      (fields (field (name "MF") "Adafruit Industries LLC"))
      (libsource (lib "eagle-import") (part "5114"))
    )
    (comp (ref "S32")
      (value "5114")
      (footprint "eagle-import:SW_5114")
      (fields (field (name "MF") "Adafruit Industries LLC"))
      (libsource (lib "eagle-import") (part "5114"))
    )
    (comp (ref "S33")
      (value "5114")
      (footprint "eagle-import:SW_5114")
      (fields (field (name "MF") "Adafruit Industries LLC"))
      (libsource (lib "eagle-import") (part "5114"))
    )
    (comp (ref "S34")
      (value "5114")
      (footprint "eagle-import:SW_5114")
      (fields (field (name "MF") "Adafruit Industries LLC"))
      (libsource (lib "eagle-import") (part "5114"))
    )
    (comp (ref "S35")
      (value "5114")
      (footprint "eagle-import:SW_5114")
      (fields (field (name "MF") "Adafruit Industries LLC"))
      (libsource (lib "eagle-import") (part "5114"))
    )
    (comp (ref "S36")
      (value "5114")
      (footprint "eagle-import:SW_5114")
      (fields (field (name "MF") "Adafruit Industries LLC"))
      (libsource (lib "eagle-import") (part "5114"))
    )
    (comp (ref "S37")
      (value "5114")
      (footprint "eagle-import:SW_5114")
      (fields (field (name "MF") "Adafruit Industries LLC"))
      (libsource (lib "eagle-import") (part "5114"))
    )
    (comp (ref "S38")
      (value "5114")
      (footprint "eagle-import:SW_5114")
      (fields (field (name "MF") "Adafruit Industries LLC"))
      (libsource (lib "eagle-import") (part "5114"))
    )
    (comp (ref "S39")
      (value "5114")
      (footprint "eagle-import:SW_5114")
      (fields (field (name "MF") "Adafruit Industries LLC"))
      (libsource (lib "eagle-import") (part "5114"))
    )
    (comp (ref "S40")
      (value "5114")
      (footprint "eagle-import:SW_5114")
      (fields (field (name "MF") "Adafruit Industries LLC"))
      (libsource (lib "eagle-import") (part "5114"))
    )
    (comp (ref "S41")
      (value "5114")
      (footprint "eagle-import:SW_5114")
      (fields (field (name "MF") "Adafruit Industries LLC"))
      (libsource (lib "eagle-import") (part "5114"))
    )
    (comp (ref "S42")
      (value "5114")
      (footprint "eagle-import:SW_5114")
      (fields (field (name "MF") "Adafruit Industries LLC"))
      (libsource (lib "eagle-import") (part "5114"))
    )
    (comp (ref "S43")
      (value "5114")
      (footprint "eagle-import:SW_5114")
      (fields (field (name "MF") "Adafruit Industries LLC"))
      (libsource (lib "eagle-import") (part "5114"))
    )
    (comp (ref "S44")
      (value "5114")
      (footprint "eagle-import:SW_5114")
      (fields (field (name "MF") "Adafruit Industries LLC"))
      (libsource (lib "eagle-import") (part "5114"))
    )
    (comp (ref "S45")
      (value "5114")
      (footprint "eagle-import:SW_5114")
      (fields (field (name "MF") "Adafruit Industries LLC"))
      (libsource (lib "eagle-import") (part "5114"))
    )
    (comp (ref "S46")
      (value "5114")
      (footprint "eagle-import:SW_5114")
      (fields (field (name "MF") "Adafruit Industries LLC"))
      (libsource (lib "eagle-import") (part "5114"))
    )
    (comp (ref "S47")
      (value "5114")
      (footprint "eagle-import:SW_5114")
      (fields (field (name "MF") "Adafruit Industries LLC"))
      (libsource (lib "eagle-import") (part "5114"))
    )
    (comp (ref "S48")
      (value "5114")
      (footprint "eagle-import:SW_5114")
      (fields (field (name "MF") "Adafruit Industries LLC"))
      (libsource (lib "eagle-import") (part "5114"))
    )
    (comp (ref "S49")
      (value "5114")
      (footprint "eagle-import:SW_5114")
      (fields (field (name "MF") "Adafruit Industries LLC"))
      (libsource (lib "eagle-import") (part "5114"))
    )
    (comp (ref "S50")
      (value "5114")
      (footprint "eagle-import:SW_5114")
      (fields (field (name "MF") "Adafruit Industries LLC"))
      (libsource (lib "eagle-import") (part "5114"))
    )
    (comp (ref "S51")
      (value "5114")
      (footprint "eagle-import:SW_5114")
      (fields (field (name "MF") "Adafruit Industries LLC"))
      (libsource (lib "eagle-import") (part "5114"))
    )
    (comp (ref "S52")
      (value "5114")
      (footprint "eagle-import:SW_5114")
      (fields (field (name "MF") "Adafruit Industries LLC"))
      (libsource (lib "eagle-import") (part "5114"))
    )
    (comp (ref "S53")
      (value "5114")
      (footprint "eagle-import:SW_5114")
      (fields (field (name "MF") "Adafruit Industries LLC"))
      (libsource (lib "eagle-import") (part "5114"))
    )
    (comp (ref "S54")
      (value "5114")
      (footprint "eagle-import:SW_5114")
      (fields (field (name "MF") "Adafruit Industries LLC"))
      (libsource (lib "eagle-import") (part "5114"))
    )
    (comp (ref "C71")
      (value "10uF")
      (footprint "eagle-import:CAPC3216X135")
      (libsource (lib "eagle-import") (part "C-USCHIP-1206(3216-METRIC)_"))
    )
    (comp (ref "C72")
      (value "10uF")
      (footprint "eagle-import:CAPC3216X135")
      (libsource (lib "eagle-import") (part "C-USCHIP-1206(3216-METRIC)_"))
    )
    (comp (ref "C73")
      (value "1uF")
      (footprint "eagle-import:CAPC2012X110")
      (libsource (lib "eagle-import") (part "C-USCHIP-0805(2012-METRIC)_"))
    )
    (comp (ref "C74")
      (value "1uF")
      (footprint "eagle-import:CAPC2012X110")
      (libsource (lib "eagle-import") (part "C-USCHIP-0805(2012-METRIC)_"))
    )
    (comp (ref "D58")
      (value "CHIP-FLAT-G_1206")
      (footprint "eagle-import:LEDC3216X75N_FLAT-G")
      (libsource (lib "eagle-import") (part "CHIP-FLAT-G_1206"))
    )
    (comp (ref "D59")
      (value "CHIP-FLAT-G_1206")
      (footprint "eagle-import:LEDC3216X75N_FLAT-G")
      (libsource (lib "eagle-import") (part "CHIP-FLAT-G_1206"))
    )
    (comp (ref "J3")
      (value "1-1775333-6CONN16_1-1775333-6_TEC")
      (footprint "eagle-import:CONN16_1-1775333-6_TEC")
      (fields
        (field (name "MANUFACTURER_PART_NUMBER") "1-1775333-6")
        (field (name "COPYRIGHT") "Copyright (C) 2025 Ultra Librarian. All rights reserved.")
      )
      (libsource (lib "eagle-import") (part "1-1775333-6CONN16_1-1775333-6_TEC"))
    )
    (comp (ref "J4")
      (value "F31L-1A7H1-11012")
      (footprint "eagle-import:AMPHENOL_F31L-1A7H1-11012")
      (fields (field (name "MANUFACTURER") "Amphenol ICC"))
      (libsource (lib "eagle-import") (part "F31L-1A7H1-11012"))
    )
    (comp (ref "JP1")
      (value "JUMPER-SMT_2_NC_TRACE_NO-SILK")
      (footprint "eagle-import:SMT-JUMPER_2_NC_TRACE_NO-SILK")
      (libsource (lib "eagle-import") (part "JUMPER-SMT_2_NC_TRACE_NO-SILK"))
    )
    (comp (ref "JP2")
      (value "JUMPER-SMT_2_NC_TRACE_NO-SILK")
      (footprint "eagle-import:SMT-JUMPER_2_NC_TRACE_NO-SILK")
      (libsource (lib "eagle-import") (part "JUMPER-SMT_2_NC_TRACE_NO-SILK"))
    )
    (comp (ref "LS1")
      (value "CMS-151135-18S-X8")
      (footprint "eagle-import:SPKR_CMS-151135-18S-X8")
      (fields (field (name "MANUFACTURER") "CUI Devices"))
      (libsource (lib "eagle-import") (part "CMS-151135-18S-X8"))
    )
    (comp (ref "LS2")
      (value "CMS-151135-18S-X8")
      (footprint "eagle-import:SPKR_CMS-151135-18S-X8")
      (fields (field (name "MANUFACTURER") "CUI Devices"))
      (libsource (lib "eagle-import") (part "CMS-151135-18S-X8"))
    )
    (comp (ref "R7")
      (value "680K")
      (footprint "eagle-import:RESC2012X65")
      (libsource (lib "eagle-import") (part "R-USCHIP-0805(2012-METRIC)_"))
    )
    (comp (ref "R8")
      (value "5.1K")
      (footprint "eagle-import:RESC2012X65")
      (libsource (lib "eagle-import") (part "R-USCHIP-0805(2012-METRIC)_"))
    )
    (comp (ref "R9")
      (value "2.2K")
      (footprint "eagle-import:RESC2012X65")
      (libsource (lib "eagle-import") (part "R-USCHIP-0805(2012-METRIC)_"))
    )
    (comp (ref "R10")
      (value "2.2K")
      (footprint "eagle-import:RESC2012X65")
      (libsource (lib "eagle-import") (part "R-USCHIP-0805(2012-METRIC)_"))
    )
    (comp (ref "R12")
      (value "10K")
      (footprint "eagle-import:RESC2012X65")
      (libsource (lib "eagle-import") (part "R-USCHIP-0805(2012-METRIC)_"))
    )
    (comp (ref "R13")
      (value "10K")
      (footprint "eagle-import:RESC2012X65")
      (libsource (lib "eagle-import") (part "R-USCHIP-0805(2012-METRIC)_"))
    )
    (comp (ref "R14")
      (value "10K")
      (footprint "eagle-import:RESC2012X65")
      (libsource (lib "eagle-import") (part "R-USCHIP-0805(2012-METRIC)_"))
    )
    (comp (ref "R15")
      (value "10K")
      (footprint "eagle-import:RESC2012X65")
      (libsource (lib "eagle-import") (part "R-USCHIP-0805(2012-METRIC)_"))
    )
    (comp (ref "S55")
      (value "SLW-1277744-3A-N-D")
      (footprint "eagle-import:SW_SLW-1277744-3A-N-D")
      (fields (field (name "MANUFACTURER") "Same Sky"))
      (libsource (lib "eagle-import") (part "SLW-1277744-3A-N-D"))
    )
    (comp (ref "S56")
      (value "SLW-1277744-3A-N-D")
      (footprint "eagle-import:SW_SLW-1277744-3A-N-D")
      (fields (field (name "MANUFACTURER") "Same Sky"))
      (libsource (lib "eagle-import") (part "SLW-1277744-3A-N-D"))
    )
    (comp (ref "S57")
      (value "SLW-1277744-3A-N-D")
      (footprint "eagle-import:SW_SLW-1277744-3A-N-D")
      (fields (field (name "MANUFACTURER") "Same Sky"))
      (libsource (lib "eagle-import") (part "SLW-1277744-3A-N-D"))
    )
    (comp (ref "S58")
      (value "SLW-1277744-3A-N-D")
      (footprint "eagle-import:SW_SLW-1277744-3A-N-D")
      (fields (field (name "MANUFACTURER") "Same Sky"))
      (libsource (lib "eagle-import") (part "SLW-1277744-3A-N-D"))
    )
    (comp (ref "S59")
      (value "SLW-1277744-3A-N-D")
      (footprint "eagle-import:SW_SLW-1277744-3A-N-D")
      (fields (field (name "MANUFACTURER") "Same Sky"))
      (libsource (lib "eagle-import") (part "SLW-1277744-3A-N-D"))
    )
    (comp (ref "S60")
      (value "SLW-1277744-3A-N-D")
      (footprint "eagle-import:SW_SLW-1277744-3A-N-D")
      (fields (field (name "MANUFACTURER") "Same Sky"))
      (libsource (lib "eagle-import") (part "SLW-1277744-3A-N-D"))
    )
    (comp (ref "S61")
      (value "SPST-NO_SWITCH_PTS645-SMT-6MM")
      (footprint "eagle-import:PTS645-SMT-6MM")
      (fields (field (name "MANUFACTURER") "C&K") (field (name "MPN") "PTS645SM43SMTR92 LFS"))
      (libsource (lib "eagle-import") (part "SPST-NO_SWITCH_PTS645-SMT-6MM"))
    )
    (comp (ref "TP10")
      (value "TPB1,27")
      (footprint "eagle-import:B1,27")
      (libsource (lib "eagle-import") (part "TPB1,27"))
    )
    (comp (ref "TP11")
      (value "TPB1,27")
      (footprint "eagle-import:B1,27")
      (libsource (lib "eagle-import") (part "TPB1,27"))
    )
    (comp (ref "TP12")
      (value "TPB1,27")
      (footprint "eagle-import:B1,27")
      (libsource (lib "eagle-import") (part "TPB1,27"))
    )
    (comp (ref "U$1")
      (value "PEC09-2120F-S0012")
      (footprint "eagle-import:PEC09-2XXXF-SXXXX")
      (libsource (lib "eagle-import") (part "PEC09-2120F-S0012"))
    )
    (comp (ref "U4")
      (value "SN74AHCT1G125DBVR")
      (footprint "eagle-import:SOT95P280X145-5N")
      (libsource (lib "eagle-import") (part "SN74AHCT1G125DBVR"))
    )
    (comp (ref "C17")
      (value "0.1uF")
      (footprint "eagle-import:CAPC2012X110")
      (libsource (lib "eagle-import") (part "C-USCHIP-0805(2012-METRIC)_"))
    )
    (comp (ref "C18")
      (value "0.1uF")
      (footprint "eagle-import:CAPC2012X110")
      (libsource (lib "eagle-import") (part "C-USCHIP-0805(2012-METRIC)_"))
    )
    (comp (ref "C19")
      (value "0.1uF")
      (footprint "eagle-import:CAPC2012X110")
      (libsource (lib "eagle-import") (part "C-USCHIP-0805(2012-METRIC)_"))
    )
    (comp (ref "C20")
      (value "0.1uF")
      (footprint "eagle-import:CAPC2012X110")
      (libsource (lib "eagle-import") (part "C-USCHIP-0805(2012-METRIC)_"))
    )
    (comp (ref "C21")
      (value "0.1uF")
      (footprint "eagle-import:CAPC2012X110")
      (libsource (lib "eagle-import") (part "C-USCHIP-0805(2012-METRIC)_"))
    )
    (comp (ref "C22")
      (value "0.1uF")
      (footprint "eagle-import:CAPC2012X110")
      (libsource (lib "eagle-import") (part "C-USCHIP-0805(2012-METRIC)_"))
    )
    (comp (ref "C23")
      (value "0.1uF")
      (footprint "eagle-import:CAPC2012X110")
      (libsource (lib "eagle-import") (part "C-USCHIP-0805(2012-METRIC)_"))
    )
    (comp (ref "C24")
      (value "0.1uF")
      (footprint "eagle-import:CAPC2012X110")
      (libsource (lib "eagle-import") (part "C-USCHIP-0805(2012-METRIC)_"))
    )
    (comp (ref "C25")
      (value "0.1uF")
      (footprint "eagle-import:CAPC2012X110")
      (libsource (lib "eagle-import") (part "C-USCHIP-0805(2012-METRIC)_"))
    )
    (comp (ref "C26")
      (value "0.1uF")
      (footprint "eagle-import:CAPC2012X110")
      (libsource (lib "eagle-import") (part "C-USCHIP-0805(2012-METRIC)_"))
    )
    (comp (ref "C27")
      (value "0.1uF")
      (footprint "eagle-import:CAPC2012X110")
      (libsource (lib "eagle-import") (part "C-USCHIP-0805(2012-METRIC)_"))
    )
    (comp (ref "C28")
      (value "0.1uF")
      (footprint "eagle-import:CAPC2012X110")
      (libsource (lib "eagle-import") (part "C-USCHIP-0805(2012-METRIC)_"))
    )
    (comp (ref "C29")
      (value "0.1uF")
      (footprint "eagle-import:CAPC2012X110")
      (libsource (lib "eagle-import") (part "C-USCHIP-0805(2012-METRIC)_"))
    )
    (comp (ref "C30")
      (value "0.1uF")
      (footprint "eagle-import:CAPC2012X110")
      (libsource (lib "eagle-import") (part "C-USCHIP-0805(2012-METRIC)_"))
    )
    (comp (ref "C31")
      (value "0.1uF")
      (footprint "eagle-import:CAPC2012X110")
      (libsource (lib "eagle-import") (part "C-USCHIP-0805(2012-METRIC)_"))
    )
    (comp (ref "C32")
      (value "0.1uF")
      (footprint "eagle-import:CAPC2012X110")
      (libsource (lib "eagle-import") (part "C-USCHIP-0805(2012-METRIC)_"))
    )
    (comp (ref "C33")
      (value "0.1uF")
      (footprint "eagle-import:CAPC2012X110")
      (libsource (lib "eagle-import") (part "C-USCHIP-0805(2012-METRIC)_"))
    )
    (comp (ref "C34")
      (value "0.1uF")
      (footprint "eagle-import:CAPC2012X110")
      (libsource (lib "eagle-import") (part "C-USCHIP-0805(2012-METRIC)_"))
    )
    (comp (ref "C35")
      (value "0.1uF")
      (footprint "eagle-import:CAPC2012X110")
      (libsource (lib "eagle-import") (part "C-USCHIP-0805(2012-METRIC)_"))
    )
    (comp (ref "C36")
      (value "0.1uF")
      (footprint "eagle-import:CAPC2012X110")
      (libsource (lib "eagle-import") (part "C-USCHIP-0805(2012-METRIC)_"))
    )
    (comp (ref "C37")
      (value "0.1uF")
      (footprint "eagle-import:CAPC2012X110")
      (libsource (lib "eagle-import") (part "C-USCHIP-0805(2012-METRIC)_"))
    )
    (comp (ref "C38")
      (value "0.1uF")
      (footprint "eagle-import:CAPC2012X110")
      (libsource (lib "eagle-import") (part "C-USCHIP-0805(2012-METRIC)_"))
    )
    (comp (ref "C39")
      (value "0.1uF")
      (footprint "eagle-import:CAPC2012X110")
      (libsource (lib "eagle-import") (part "C-USCHIP-0805(2012-METRIC)_"))
    )
    (comp (ref "C40")
      (value "0.1uF")
      (footprint "eagle-import:CAPC2012X110")
      (libsource (lib "eagle-import") (part "C-USCHIP-0805(2012-METRIC)_"))
    )
    (comp (ref "C41")
      (value "0.1uF")
      (footprint "eagle-import:CAPC2012X110")
      (libsource (lib "eagle-import") (part "C-USCHIP-0805(2012-METRIC)_"))
    )
    (comp (ref "C42")
      (value "0.1uF")
      (footprint "eagle-import:CAPC2012X110")
      (libsource (lib "eagle-import") (part "C-USCHIP-0805(2012-METRIC)_"))
    )
    (comp (ref "C43")
      (value "0.1uF")
      (footprint "eagle-import:CAPC2012X110")
      (libsource (lib "eagle-import") (part "C-USCHIP-0805(2012-METRIC)_"))
    )
    (comp (ref "C44")
      (value "0.1uF")
      (footprint "eagle-import:CAPC2012X110")
      (libsource (lib "eagle-import") (part "C-USCHIP-0805(2012-METRIC)_"))
    )
    (comp (ref "C45")
      (value "0.1uF")
      (footprint "eagle-import:CAPC2012X110")
      (libsource (lib "eagle-import") (part "C-USCHIP-0805(2012-METRIC)_"))
    )
    (comp (ref "C46")
      (value "0.1uF")
      (footprint "eagle-import:CAPC2012X110")
      (libsource (lib "eagle-import") (part "C-USCHIP-0805(2012-METRIC)_"))
    )
    (comp (ref "C47")
      (value "0.1uF")
      (footprint "eagle-import:CAPC2012X110")
      (libsource (lib "eagle-import") (part "C-USCHIP-0805(2012-METRIC)_"))
    )
    (comp (ref "C48")
      (value "0.1uF")
      (footprint "eagle-import:CAPC2012X110")
      (libsource (lib "eagle-import") (part "C-USCHIP-0805(2012-METRIC)_"))
    )
    (comp (ref "C49")
      (value "0.1uF")
      (footprint "eagle-import:CAPC2012X110")
      (libsource (lib "eagle-import") (part "C-USCHIP-0805(2012-METRIC)_"))
    )
    (comp (ref "C50")
      (value "0.1uF")
      (footprint "eagle-import:CAPC2012X110")
      (libsource (lib "eagle-import") (part "C-USCHIP-0805(2012-METRIC)_"))
    )
    (comp (ref "C51")
      (value "0.1uF")
      (footprint "eagle-import:CAPC2012X110")
      (libsource (lib "eagle-import") (part "C-USCHIP-0805(2012-METRIC)_"))
    )
    (comp (ref "C52")
      (value "0.1uF")
      (footprint "eagle-import:CAPC2012X110")
      (libsource (lib "eagle-import") (part "C-USCHIP-0805(2012-METRIC)_"))
    )
    (comp (ref "C53")
      (value "0.1uF")
      (footprint "eagle-import:CAPC2012X110")
      (libsource (lib "eagle-import") (part "C-USCHIP-0805(2012-METRIC)_"))
    )
    (comp (ref "C54")
      (value "0.1uF")
      (footprint "eagle-import:CAPC2012X110")
      (libsource (lib "eagle-import") (part "C-USCHIP-0805(2012-METRIC)_"))
    )
    (comp (ref "C55")
      (value "0.1uF")
      (footprint "eagle-import:CAPC2012X110")
      (libsource (lib "eagle-import") (part "C-USCHIP-0805(2012-METRIC)_"))
    )
    (comp (ref "C56")
      (value "0.1uF")
      (footprint "eagle-import:CAPC2012X110")
      (libsource (lib "eagle-import") (part "C-USCHIP-0805(2012-METRIC)_"))
    )
    (comp (ref "C57")
      (value "0.1uF")
      (footprint "eagle-import:CAPC2012X110")
      (libsource (lib "eagle-import") (part "C-USCHIP-0805(2012-METRIC)_"))
    )
    (comp (ref "C58")
      (value "0.1uF")
      (footprint "eagle-import:CAPC2012X110")
      (libsource (lib "eagle-import") (part "C-USCHIP-0805(2012-METRIC)_"))
    )
    (comp (ref "C59")
      (value "0.1uF")
      (footprint "eagle-import:CAPC2012X110")
      (libsource (lib "eagle-import") (part "C-USCHIP-0805(2012-METRIC)_"))
    )
    (comp (ref "C60")
      (value "0.1uF")
      (footprint "eagle-import:CAPC2012X110")
      (libsource (lib "eagle-import") (part "C-USCHIP-0805(2012-METRIC)_"))
    )
    (comp (ref "C61")
      (value "0.1uF")
      (footprint "eagle-import:CAPC2012X110")
      (libsource (lib "eagle-import") (part "C-USCHIP-0805(2012-METRIC)_"))
    )
    (comp (ref "C62")
      (value "0.1uF")
      (footprint "eagle-import:CAPC2012X110")
      (libsource (lib "eagle-import") (part "C-USCHIP-0805(2012-METRIC)_"))
    )
    (comp (ref "C63")
      (value "0.1uF")
      (footprint "eagle-import:CAPC2012X110")
      (libsource (lib "eagle-import") (part "C-USCHIP-0805(2012-METRIC)_"))
    )
    (comp (ref "C64")
      (value "0.1uF")
      (footprint "eagle-import:CAPC2012X110")
      (libsource (lib "eagle-import") (part "C-USCHIP-0805(2012-METRIC)_"))
    )
    (comp (ref "C65")
      (value "0.1uF")
      (footprint "eagle-import:CAPC2012X110")
      (libsource (lib "eagle-import") (part "C-USCHIP-0805(2012-METRIC)_"))
    )
    (comp (ref "C66")
      (value "0.1uF")
      (footprint "eagle-import:CAPC2012X110")
      (libsource (lib "eagle-import") (part "C-USCHIP-0805(2012-METRIC)_"))
    )
    (comp (ref "C67")
      (value "0.1uF")
      (footprint "eagle-import:CAPC2012X110")
      (libsource (lib "eagle-import") (part "C-USCHIP-0805(2012-METRIC)_"))
    )
    (comp (ref "C68")
      (value "0.1uF")
      (footprint "eagle-import:CAPC2012X110")
      (libsource (lib "eagle-import") (part "C-USCHIP-0805(2012-METRIC)_"))
    )
    (comp (ref "C69")
      (value "0.1uF")
      (footprint "eagle-import:CAPC2012X110")
      (libsource (lib "eagle-import") (part "C-USCHIP-0805(2012-METRIC)_"))
    )
    (comp (ref "C70")
      (value "0.1uF")
      (footprint "eagle-import:CAPC2012X110")
      (libsource (lib "eagle-import") (part "C-USCHIP-0805(2012-METRIC)_"))
    )
    (comp (ref "LED1")
      (value "SK6812-EJ")
      (footprint "eagle-import:LED_SK6812-E")
      (fields (field (name "MF") "DONGGUANG OPSCO OPTOELECTRONICS CO., LTD") (field (name "MP") "SK6812-E"))
      (libsource (lib "eagle-import") (part "SK6812-EJ"))
    )
    (comp (ref "LED2")
      (value "SK6812-EJ")
      (footprint "eagle-import:LED_SK6812-E")
      (fields (field (name "MF") "DONGGUANG OPSCO OPTOELECTRONICS CO., LTD") (field (name "MP") "SK6812-E"))
      (libsource (lib "eagle-import") (part "SK6812-EJ"))
    )
    (comp (ref "LED3")
      (value "SK6812-EJ")
      (footprint "eagle-import:LED_SK6812-E")
      (fields (field (name "MF") "DONGGUANG OPSCO OPTOELECTRONICS CO., LTD") (field (name "MP") "SK6812-E"))
      (libsource (lib "eagle-import") (part "SK6812-EJ"))
    )
    (comp (ref "LED4")
      (value "SK6812-EJ")
      (footprint "eagle-import:LED_SK6812-E")
      (fields (field (name "MF") "DONGGUANG OPSCO OPTOELECTRONICS CO., LTD") (field (name "MP") "SK6812-E"))
      (libsource (lib "eagle-import") (part "SK6812-EJ"))
    )
    (comp (ref "LED5")
      (value "SK6812-EJ")
      (footprint "eagle-import:LED_SK6812-E")
      (fields (field (name "MF") "DONGGUANG OPSCO OPTOELECTRONICS CO., LTD") (field (name "MP") "SK6812-E"))
      (libsource (lib "eagle-import") (part "SK6812-EJ"))
    )
    (comp (ref "LED6")
      (value "SK6812-EJ")
      (footprint "eagle-import:LED_SK6812-E")
      (fields (field (name "MF") "DONGGUANG OPSCO OPTOELECTRONICS CO., LTD") (field (name "MP") "SK6812-E"))
      (libsource (lib "eagle-import") (part "SK6812-EJ"))
    )
    (comp (ref "LED7")
      (value "SK6812-EJ")
      (footprint "eagle-import:LED_SK6812-E")
      (fields (field (name "MF") "DONGGUANG OPSCO OPTOELECTRONICS CO., LTD") (field (name "MP") "SK6812-E"))
      (libsource (lib "eagle-import") (part "SK6812-EJ"))
    )
    (comp (ref "LED8")
      (value "SK6812-EJ")
      (footprint "eagle-import:LED_SK6812-E")
      (fields (field (name "MF") "DONGGUANG OPSCO OPTOELECTRONICS CO., LTD") (field (name "MP") "SK6812-E"))
      (libsource (lib "eagle-import") (part "SK6812-EJ"))
    )
    (comp (ref "LED9")
      (value "SK6812-EJ")
      (footprint "eagle-import:LED_SK6812-E")
      (fields (field (name "MF") "DONGGUANG OPSCO OPTOELECTRONICS CO., LTD") (field (name "MP") "SK6812-E"))
      (libsource (lib "eagle-import") (part "SK6812-EJ"))
    )
    (comp (ref "LED10")
      (value "SK6812-EJ")
      (footprint "eagle-import:LED_SK6812-E")
      (fields (field (name "MF") "DONGGUANG OPSCO OPTOELECTRONICS CO., LTD") (field (name "MP") "SK6812-E"))
      (libsource (lib "eagle-import") (part "SK6812-EJ"))
    )
    (comp (ref "LED11")
      (value "SK6812-EJ")
      (footprint "eagle-import:LED_SK6812-E")
      (fields (field (name "MF") "DONGGUANG OPSCO OPTOELECTRONICS CO., LTD") (field (name "MP") "SK6812-E"))
      (libsource (lib "eagle-import") (part "SK6812-EJ"))
    )
    (comp (ref "LED12")
      (value "SK6812-EJ")
      (footprint "eagle-import:LED_SK6812-E")
      (fields (field (name "MF") "DONGGUANG OPSCO OPTOELECTRONICS CO., LTD") (field (name "MP") "SK6812-E"))
      (libsource (lib "eagle-import") (part "SK6812-EJ"))
    )
    (comp (ref "LED13")
      (value "SK6812-EJ")
      (footprint "eagle-import:LED_SK6812-E")
      (fields (field (name "MF") "DONGGUANG OPSCO OPTOELECTRONICS CO., LTD") (field (name "MP") "SK6812-E"))
      (libsource (lib "eagle-import") (part "SK6812-EJ"))
    )
    (comp (ref "LED14")
      (value "SK6812-EJ")
      (footprint "eagle-import:LED_SK6812-E")
      (fields (field (name "MF") "DONGGUANG OPSCO OPTOELECTRONICS CO., LTD") (field (name "MP") "SK6812-E"))
      (libsource (lib "eagle-import") (part "SK6812-EJ"))
    )
    (comp (ref "LED15")
      (value "SK6812-EJ")
      (footprint "eagle-import:LED_SK6812-E")
      (fields (field (name "MF") "DONGGUANG OPSCO OPTOELECTRONICS CO., LTD") (field (name "MP") "SK6812-E"))
      (libsource (lib "eagle-import") (part "SK6812-EJ"))
    )
    (comp (ref "LED16")
      (value "SK6812-EJ")
      (footprint "eagle-import:LED_SK6812-E")
      (fields (field (name "MF") "DONGGUANG OPSCO OPTOELECTRONICS CO., LTD") (field (name "MP") "SK6812-E"))
      (libsource (lib "eagle-import") (part "SK6812-EJ"))
    )
    (comp (ref "LED17")
      (value "SK6812-EJ")
      (footprint "eagle-import:LED_SK6812-E")
      (fields (field (name "MF") "DONGGUANG OPSCO OPTOELECTRONICS CO., LTD") (field (name "MP") "SK6812-E"))
      (libsource (lib "eagle-import") (part "SK6812-EJ"))
    )
    (comp (ref "LED18")
      (value "SK6812-EJ")
      (footprint "eagle-import:LED_SK6812-E")
      (fields (field (name "MF") "DONGGUANG OPSCO OPTOELECTRONICS CO., LTD") (field (name "MP") "SK6812-E"))
      (libsource (lib "eagle-import") (part "SK6812-EJ"))
    )
    (comp (ref "LED19")
      (value "SK6812-EJ")
      (footprint "eagle-import:LED_SK6812-E")
      (fields (field (name "MF") "DONGGUANG OPSCO OPTOELECTRONICS CO., LTD") (field (name "MP") "SK6812-E"))
      (libsource (lib "eagle-import") (part "SK6812-EJ"))
    )
    (comp (ref "LED20")
      (value "SK6812-EJ")
      (footprint "eagle-import:LED_SK6812-E")
      (fields (field (name "MF") "DONGGUANG OPSCO OPTOELECTRONICS CO., LTD") (field (name "MP") "SK6812-E"))
      (libsource (lib "eagle-import") (part "SK6812-EJ"))
    )
    (comp (ref "LED21")
      (value "SK6812-EJ")
      (footprint "eagle-import:LED_SK6812-E")
      (fields (field (name "MF") "DONGGUANG OPSCO OPTOELECTRONICS CO., LTD") (field (name "MP") "SK6812-E"))
      (libsource (lib "eagle-import") (part "SK6812-EJ"))
    )
    (comp (ref "LED22")
      (value "SK6812-EJ")
      (footprint "eagle-import:LED_SK6812-E")
      (fields (field (name "MF") "DONGGUANG OPSCO OPTOELECTRONICS CO., LTD") (field (name "MP") "SK6812-E"))
      (libsource (lib "eagle-import") (part "SK6812-EJ"))
    )
    (comp (ref "LED23")
      (value "SK6812-EJ")
      (footprint "eagle-import:LED_SK6812-E")
      (fields (field (name "MF") "DONGGUANG OPSCO OPTOELECTRONICS CO., LTD") (field (name "MP") "SK6812-E"))
      (libsource (lib "eagle-import") (part "SK6812-EJ"))
    )
    (comp (ref "LED24")
      (value "SK6812-EJ")
      (footprint "eagle-import:LED_SK6812-E")
      (fields (field (name "MF") "DONGGUANG OPSCO OPTOELECTRONICS CO., LTD") (field (name "MP") "SK6812-E"))
      (libsource (lib "eagle-import") (part "SK6812-EJ"))
    )
    (comp (ref "LED25")
      (value "SK6812-EJ")
      (footprint "eagle-import:LED_SK6812-E")
      (fields (field (name "MF") "DONGGUANG OPSCO OPTOELECTRONICS CO., LTD") (field (name "MP") "SK6812-E"))
      (libsource (lib "eagle-import") (part "SK6812-EJ"))
    )
    (comp (ref "LED26")
      (value "SK6812-EJ")
      (footprint "eagle-import:LED_SK6812-E")
      (fields (field (name "MF") "DONGGUANG OPSCO OPTOELECTRONICS CO., LTD") (field (name "MP") "SK6812-E"))
      (libsource (lib "eagle-import") (part "SK6812-EJ"))
    )
    (comp (ref "LED27")
      (value "SK6812-EJ")
      (footprint "eagle-import:LED_SK6812-E")
      (fields (field (name "MF") "DONGGUANG OPSCO OPTOELECTRONICS CO., LTD") (field (name "MP") "SK6812-E"))
      (libsource (lib "eagle-import") (part "SK6812-EJ"))
    )
    (comp (ref "LED28")
      (value "SK6812-EJ")
      (footprint "eagle-import:LED_SK6812-E")
      (fields (field (name "MF") "DONGGUANG OPSCO OPTOELECTRONICS CO., LTD") (field (name "MP") "SK6812-E"))
      (libsource (lib "eagle-import") (part "SK6812-EJ"))
    )
    (comp (ref "LED29")
      (value "SK6812-EJ")
      (footprint "eagle-import:LED_SK6812-E")
      (fields (field (name "MF") "DONGGUANG OPSCO OPTOELECTRONICS CO., LTD") (field (name "MP") "SK6812-E"))
      (libsource (lib "eagle-import") (part "SK6812-EJ"))
    )
    (comp (ref "LED30")
      (value "SK6812-EJ")
      (footprint "eagle-import:LED_SK6812-E")
      (fields (field (name "MF") "DONGGUANG OPSCO OPTOELECTRONICS CO., LTD") (field (name "MP") "SK6812-E"))
      (libsource (lib "eagle-import") (part "SK6812-EJ"))
    )
    (comp (ref "LED31")
      (value "SK6812-EJ")
      (footprint "eagle-import:LED_SK6812-E")
      (fields (field (name "MF") "DONGGUANG OPSCO OPTOELECTRONICS CO., LTD") (field (name "MP") "SK6812-E"))
      (libsource (lib "eagle-import") (part "SK6812-EJ"))
    )
    (comp (ref "LED32")
      (value "SK6812-EJ")
      (footprint "eagle-import:LED_SK6812-E")
      (fields (field (name "MF") "DONGGUANG OPSCO OPTOELECTRONICS CO., LTD") (field (name "MP") "SK6812-E"))
      (libsource (lib "eagle-import") (part "SK6812-EJ"))
    )
    (comp (ref "LED33")
      (value "SK6812-EJ")
      (footprint "eagle-import:LED_SK6812-E")
      (fields (field (name "MF") "DONGGUANG OPSCO OPTOELECTRONICS CO., LTD") (field (name "MP") "SK6812-E"))
      (libsource (lib "eagle-import") (part "SK6812-EJ"))
    )
    (comp (ref "LED34")
      (value "SK6812-EJ")
      (footprint "eagle-import:LED_SK6812-E")
      (fields (field (name "MF") "DONGGUANG OPSCO OPTOELECTRONICS CO., LTD") (field (name "MP") "SK6812-E"))
      (libsource (lib "eagle-import") (part "SK6812-EJ"))
    )
    (comp (ref "LED35")
      (value "SK6812-EJ")
      (footprint "eagle-import:LED_SK6812-E")
      (fields (field (name "MF") "DONGGUANG OPSCO OPTOELECTRONICS CO., LTD") (field (name "MP") "SK6812-E"))
      (libsource (lib "eagle-import") (part "SK6812-EJ"))
    )
    (comp (ref "LED36")
      (value "SK6812-EJ")
      (footprint "eagle-import:LED_SK6812-E")
      (fields (field (name "MF") "DONGGUANG OPSCO OPTOELECTRONICS CO., LTD") (field (name "MP") "SK6812-E"))
      (libsource (lib "eagle-import") (part "SK6812-EJ"))
    )
    (comp (ref "LED37")
      (value "SK6812-EJ")
      (footprint "eagle-import:LED_SK6812-E")
      (fields (field (name "MF") "DONGGUANG OPSCO OPTOELECTRONICS CO., LTD") (field (name "MP") "SK6812-E"))
      (libsource (lib "eagle-import") (part "SK6812-EJ"))
    )
    (comp (ref "LED38")
      (value "SK6812-EJ")
      (footprint "eagle-import:LED_SK6812-E")
      (fields (field (name "MF") "DONGGUANG OPSCO OPTOELECTRONICS CO., LTD") (field (name "MP") "SK6812-E"))
      (libsource (lib "eagle-import") (part "SK6812-EJ"))
    )
    (comp (ref "LED39")
      (value "SK6812-EJ")
      (footprint "eagle-import:LED_SK6812-E")
      (fields (field (name "MF") "DONGGUANG OPSCO OPTOELECTRONICS CO., LTD") (field (name "MP") "SK6812-E"))
      (libsource (lib "eagle-import") (part "SK6812-EJ"))
    )
    (comp (ref "LED40")
      (value "SK6812-EJ")
      (footprint "eagle-import:LED_SK6812-E")
      (fields (field (name "MF") "DONGGUANG OPSCO OPTOELECTRONICS CO., LTD") (field (name "MP") "SK6812-E"))
      (libsource (lib "eagle-import") (part "SK6812-EJ"))
    )
    (comp (ref "LED41")
      (value "SK6812-EJ")
      (footprint "eagle-import:LED_SK6812-E")
      (fields (field (name "MF") "DONGGUANG OPSCO OPTOELECTRONICS CO., LTD") (field (name "MP") "SK6812-E"))
      (libsource (lib "eagle-import") (part "SK6812-EJ"))
    )
    (comp (ref "LED42")
      (value "SK6812-EJ")
      (footprint "eagle-import:LED_SK6812-E")
      (fields (field (name "MF") "DONGGUANG OPSCO OPTOELECTRONICS CO., LTD") (field (name "MP") "SK6812-E"))
      (libsource (lib "eagle-import") (part "SK6812-EJ"))
    )
    (comp (ref "LED43")
      (value "SK6812-EJ")
      (footprint "eagle-import:LED_SK6812-E")
      (fields (field (name "MF") "DONGGUANG OPSCO OPTOELECTRONICS CO., LTD") (field (name "MP") "SK6812-E"))
      (libsource (lib "eagle-import") (part "SK6812-EJ"))
    )
    (comp (ref "LED44")
      (value "SK6812-EJ")
      (footprint "eagle-import:LED_SK6812-E")
      (fields (field (name "MF") "DONGGUANG OPSCO OPTOELECTRONICS CO., LTD") (field (name "MP") "SK6812-E"))
      (libsource (lib "eagle-import") (part "SK6812-EJ"))
    )
    (comp (ref "LED45")
      (value "SK6812-EJ")
      (footprint "eagle-import:LED_SK6812-E")
      (fields (field (name "MF") "DONGGUANG OPSCO OPTOELECTRONICS CO., LTD") (field (name "MP") "SK6812-E"))
      (libsource (lib "eagle-import") (part "SK6812-EJ"))
    )
    (comp (ref "LED46")
      (value "SK6812-EJ")
      (footprint "eagle-import:LED_SK6812-E")
      (fields (field (name "MF") "DONGGUANG OPSCO OPTOELECTRONICS CO., LTD") (field (name "MP") "SK6812-E"))
      (libsource (lib "eagle-import") (part "SK6812-EJ"))
    )
    (comp (ref "LED47")
      (value "SK6812-EJ")
      (footprint "eagle-import:LED_SK6812-E")
      (fields (field (name "MF") "DONGGUANG OPSCO OPTOELECTRONICS CO., LTD") (field (name "MP") "SK6812-E"))
      (libsource (lib "eagle-import") (part "SK6812-EJ"))
    )
    (comp (ref "LED48")
      (value "SK6812-EJ")
      (footprint "eagle-import:LED_SK6812-E")
      (fields (field (name "MF") "DONGGUANG OPSCO OPTOELECTRONICS CO., LTD") (field (name "MP") "SK6812-E"))
      (libsource (lib "eagle-import") (part "SK6812-EJ"))
    )
    (comp (ref "LED49")
      (value "SK6812-EJ")
      (footprint "eagle-import:LED_SK6812-E")
      (fields (field (name "MF") "DONGGUANG OPSCO OPTOELECTRONICS CO., LTD") (field (name "MP") "SK6812-E"))
      (libsource (lib "eagle-import") (part "SK6812-EJ"))
    )
    (comp (ref "LED50")
      (value "SK6812-EJ")
      (footprint "eagle-import:LED_SK6812-E")
      (fields (field (name "MF") "DONGGUANG OPSCO OPTOELECTRONICS CO., LTD") (field (name "MP") "SK6812-E"))
      (libsource (lib "eagle-import") (part "SK6812-EJ"))
    )
    (comp (ref "LED51")
      (value "SK6812-EJ")
      (footprint "eagle-import:LED_SK6812-E")
      (fields (field (name "MF") "DONGGUANG OPSCO OPTOELECTRONICS CO., LTD") (field (name "MP") "SK6812-E"))
      (libsource (lib "eagle-import") (part "SK6812-EJ"))
    )
    (comp (ref "LED52")
      (value "SK6812-EJ")
      (footprint "eagle-import:LED_SK6812-E")
      (fields (field (name "MF") "DONGGUANG OPSCO OPTOELECTRONICS CO., LTD") (field (name "MP") "SK6812-E"))
      (libsource (lib "eagle-import") (part "SK6812-EJ"))
    )
    (comp (ref "LED53")
      (value "SK6812-EJ")
      (footprint "eagle-import:LED_SK6812-E")
      (fields (field (name "MF") "DONGGUANG OPSCO OPTOELECTRONICS CO., LTD") (field (name "MP") "SK6812-E"))
      (libsource (lib "eagle-import") (part "SK6812-EJ"))
    )
    (comp (ref "LED54")
      (value "SK6812-EJ")
      (footprint "eagle-import:LED_SK6812-E")
      (fields (field (name "MF") "DONGGUANG OPSCO OPTOELECTRONICS CO., LTD") (field (name "MP") "SK6812-E"))
      (libsource (lib "eagle-import") (part "SK6812-EJ"))
    )
  )
  (nets
    (net (code "1") (name "1V1") (class "Default")
      (node (ref "C10") (pin "1") (pinfunction "1_1") (pintype "passive"))
      (node (ref "C11") (pin "1") (pinfunction "1_1") (pintype "passive"))
      (node (ref "C12") (pin "1") (pinfunction "1_1") (pintype "passive"))
      (node (ref "U1") (pin "23") (pinfunction "DVDD_23") (pintype "power_in"))
      (node (ref "U1") (pin "45") (pinfunction "VREG_VOUT_45") (pintype "output"))
      (node (ref "U1") (pin "50") (pinfunction "DVDD_50") (pintype "power_in"))
    )
    (net (code "2") (name "3V3") (class "Default")
      (node (ref "C13") (pin "1") (pinfunction "1_1") (pintype "passive"))
      (node (ref "C16") (pin "1") (pinfunction "1_1") (pintype "passive"))
      (node (ref "C2") (pin "1") (pinfunction "1_1") (pintype "passive"))
      (node (ref "C3") (pin "1") (pinfunction "1_1") (pintype "passive"))
      (node (ref "C4") (pin "1") (pinfunction "1_1") (pintype "passive"))
      (node (ref "C5") (pin "1") (pinfunction "1_1") (pintype "passive"))
      (node (ref "C6") (pin "1") (pinfunction "1_1") (pintype "passive"))
      (node (ref "C7") (pin "1") (pinfunction "1_1") (pintype "passive"))
      (node (ref "C8") (pin "1") (pinfunction "1_1") (pintype "passive"))
      (node (ref "C9") (pin "1") (pinfunction "1_1") (pintype "passive"))
      (node (ref "J3") (pin "10") (pinfunction "10_10") (pintype "passive"))
      (node (ref "J3") (pin "12") (pinfunction "12_12") (pintype "passive"))
      (node (ref "J4") (pin "1") (pinfunction "1_1") (pintype "passive"))
      (node (ref "R12") (pin "2") (pinfunction "2_2") (pintype "passive"))
      (node (ref "R13") (pin "2") (pinfunction "2_2") (pintype "passive"))
      (node (ref "R14") (pin "2") (pinfunction "2_2") (pintype "passive"))
      (node (ref "R15") (pin "2") (pinfunction "2_2") (pintype "passive"))
      (node (ref "R4") (pin "2") (pinfunction "2_2") (pintype "passive"))
      (node (ref "R5") (pin "2") (pinfunction "2_2") (pintype "passive"))
      (node (ref "TP12") (pin "TP") (pinfunction "TP_TP") (pintype "input"))
      (node (ref "TP3") (pin "TP") (pinfunction "TP_TP") (pintype "input"))
      (node (ref "U1") (pin "1") (pinfunction "IOVDD_1") (pintype "power_in"))
      (node (ref "U1") (pin "10") (pinfunction "IOVDD_10") (pintype "power_in"))
      (node (ref "U1") (pin "22") (pinfunction "IOVDD_22") (pintype "power_in"))
      (node (ref "U1") (pin "33") (pinfunction "IOVDD_33") (pintype "power_in"))
      (node (ref "U1") (pin "42") (pinfunction "IOVDD_42") (pintype "power_in"))
      (node (ref "U1") (pin "43") (pinfunction "ADC_AVDD_43") (pintype "power_in"))
      (node (ref "U1") (pin "44") (pinfunction "VREG_VIN_44") (pintype "input"))
      (node (ref "U1") (pin "48") (pinfunction "USB_VDD_48") (pintype "power_in"))
      (node (ref "U1") (pin "49") (pinfunction "IOVDD_49") (pintype "power_in"))
      (node (ref "U2") (pin "5") (pinfunction "VOUT_5") (pintype "passive"))
      (node (ref "U3") (pin "8") (pinfunction "VCC_8") (pintype "power_in"))
    )
    (net (code "3") (name "5V") (class "Default")
      (node (ref "C1") (pin "1") (pinfunction "1_1") (pintype "passive"))
      (node (ref "C17") (pin "2") (pinfunction "2_2") (pintype "passive"))
      (node (ref "C18") (pin "2") (pinfunction "2_2") (pintype "passive"))
      (node (ref "C19") (pin "2") (pinfunction "2_2") (pintype "passive"))
      (node (ref "C20") (pin "2") (pinfunction "2_2") (pintype "passive"))
      (node (ref "C21") (pin "2") (pinfunction "2_2") (pintype "passive"))
      (node (ref "C22") (pin "2") (pinfunction "2_2") (pintype "passive"))
      (node (ref "C23") (pin "2") (pinfunction "2_2") (pintype "passive"))
      (node (ref "C24") (pin "2") (pinfunction "2_2") (pintype "passive"))
      (node (ref "C25") (pin "2") (pinfunction "2_2") (pintype "passive"))
      (node (ref "C26") (pin "2") (pinfunction "2_2") (pintype "passive"))
      (node (ref "C27") (pin "2") (pinfunction "2_2") (pintype "passive"))
      (node (ref "C28") (pin "2") (pinfunction "2_2") (pintype "passive"))
      (node (ref "C29") (pin "2") (pinfunction "2_2") (pintype "passive"))
      (node (ref "C30") (pin "2") (pinfunction "2_2") (pintype "passive"))
      (node (ref "C31") (pin "2") (pinfunction "2_2") (pintype "passive"))
      (node (ref "C32") (pin "2") (pinfunction "2_2") (pintype "passive"))
      (node (ref "C33") (pin "2") (pinfunction "2_2") (pintype "passive"))
      (node (ref "C34") (pin "2") (pinfunction "2_2") (pintype "passive"))
      (node (ref "C35") (pin "2") (pinfunction "2_2") (pintype "passive"))
      (node (ref "C36") (pin "2") (pinfunction "2_2") (pintype "passive"))
      (node (ref "C37") (pin "2") (pinfunction "2_2") (pintype "passive"))
      (node (ref "C38") (pin "2") (pinfunction "2_2") (pintype "passive"))
      (node (ref "C39") (pin "2") (pinfunction "2_2") (pintype "passive"))
      (node (ref "C40") (pin "2") (pinfunction "2_2") (pintype "passive"))
      (node (ref "C41") (pin "2") (pinfunction "2_2") (pintype "passive"))
      (node (ref "C42") (pin "2") (pinfunction "2_2") (pintype "passive"))
      (node (ref "C43") (pin "2") (pinfunction "2_2") (pintype "passive"))
      (node (ref "C44") (pin "2") (pinfunction "2_2") (pintype "passive"))
      (node (ref "C45") (pin "2") (pinfunction "2_2") (pintype "passive"))
      (node (ref "C46") (pin "2") (pinfunction "2_2") (pintype "passive"))
      (node (ref "C47") (pin "2") (pinfunction "2_2") (pintype "passive"))
      (node (ref "C48") (pin "2") (pinfunction "2_2") (pintype "passive"))
      (node (ref "C49") (pin "2") (pinfunction "2_2") (pintype "passive"))
      (node (ref "C50") (pin "2") (pinfunction "2_2") (pintype "passive"))
      (node (ref "C51") (pin "2") (pinfunction "2_2") (pintype "passive"))
      (node (ref "C52") (pin "2") (pinfunction "2_2") (pintype "passive"))
      (node (ref "C53") (pin "2") (pinfunction "2_2") (pintype "passive"))
      (node (ref "C54") (pin "2") (pinfunction "2_2") (pintype "passive"))
      (node (ref "C55") (pin "2") (pinfunction "2_2") (pintype "passive"))
      (node (ref "C56") (pin "2") (pinfunction "2_2") (pintype "passive"))
      (node (ref "C57") (pin "2") (pinfunction "2_2") (pintype "passive"))
      (node (ref "C58") (pin "2") (pinfunction "2_2") (pintype "passive"))
      (node (ref "C59") (pin "2") (pinfunction "2_2") (pintype "passive"))
      (node (ref "C60") (pin "2") (pinfunction "2_2") (pintype "passive"))
      (node (ref "C61") (pin "2") (pinfunction "2_2") (pintype "passive"))
      (node (ref "C62") (pin "2") (pinfunction "2_2") (pintype "passive"))
      (node (ref "C63") (pin "2") (pinfunction "2_2") (pintype "passive"))
      (node (ref "C64") (pin "2") (pinfunction "2_2") (pintype "passive"))
      (node (ref "C65") (pin "2") (pinfunction "2_2") (pintype "passive"))
      (node (ref "C66") (pin "2") (pinfunction "2_2") (pintype "passive"))
      (node (ref "C67") (pin "2") (pinfunction "2_2") (pintype "passive"))
      (node (ref "C68") (pin "2") (pinfunction "2_2") (pintype "passive"))
      (node (ref "C69") (pin "2") (pinfunction "2_2") (pintype "passive"))
      (node (ref "C70") (pin "2") (pinfunction "2_2") (pintype "passive"))
      (node (ref "D58") (pin "A") (pinfunction "A_A") (pintype "passive"))
      (node (ref "D59") (pin "A") (pinfunction "A_A") (pintype "passive"))
      (node (ref "J2") (pin "A3") (pinfunction "A3_A3") (pintype "passive"))
      (node (ref "J2") (pin "A4") (pinfunction "A4_A4") (pintype "passive"))
      (node (ref "LED1") (pin "1") (pinfunction "VDD_1") (pintype "power_in"))
      (node (ref "LED10") (pin "1") (pinfunction "VDD_1") (pintype "power_in"))
      (node (ref "LED11") (pin "1") (pinfunction "VDD_1") (pintype "power_in"))
      (node (ref "LED12") (pin "1") (pinfunction "VDD_1") (pintype "power_in"))
      (node (ref "LED13") (pin "1") (pinfunction "VDD_1") (pintype "power_in"))
      (node (ref "LED14") (pin "1") (pinfunction "VDD_1") (pintype "power_in"))
      (node (ref "LED15") (pin "1") (pinfunction "VDD_1") (pintype "power_in"))
      (node (ref "LED16") (pin "1") (pinfunction "VDD_1") (pintype "power_in"))
      (node (ref "LED17") (pin "1") (pinfunction "VDD_1") (pintype "power_in"))
      (node (ref "LED18") (pin "1") (pinfunction "VDD_1") (pintype "power_in"))
      (node (ref "LED19") (pin "1") (pinfunction "VDD_1") (pintype "power_in"))
      (node (ref "LED2") (pin "1") (pinfunction "VDD_1") (pintype "power_in"))
      (node (ref "LED20") (pin "1") (pinfunction "VDD_1") (pintype "power_in"))
      (node (ref "LED21") (pin "1") (pinfunction "VDD_1") (pintype "power_in"))
      (node (ref "LED22") (pin "1") (pinfunction "VDD_1") (pintype "power_in"))
      (node (ref "LED23") (pin "1") (pinfunction "VDD_1") (pintype "power_in"))
      (node (ref "LED24") (pin "1") (pinfunction "VDD_1") (pintype "power_in"))
      (node (ref "LED25") (pin "1") (pinfunction "VDD_1") (pintype "power_in"))
      (node (ref "LED26") (pin "1") (pinfunction "VDD_1") (pintype "power_in"))
      (node (ref "LED27") (pin "1") (pinfunction "VDD_1") (pintype "power_in"))
      (node (ref "LED28") (pin "1") (pinfunction "VDD_1") (pintype "power_in"))
      (node (ref "LED29") (pin "1") (pinfunction "VDD_1") (pintype "power_in"))
      (node (ref "LED3") (pin "1") (pinfunction "VDD_1") (pintype "power_in"))
      (node (ref "LED30") (pin "1") (pinfunction "VDD_1") (pintype "power_in"))
      (node (ref "LED31") (pin "1") (pinfunction "VDD_1") (pintype "power_in"))
      (node (ref "LED32") (pin "1") (pinfunction "VDD_1") (pintype "power_in"))
      (node (ref "LED33") (pin "1") (pinfunction "VDD_1") (pintype "power_in"))
      (node (ref "LED34") (pin "1") (pinfunction "VDD_1") (pintype "power_in"))
      (node (ref "LED35") (pin "1") (pinfunction "VDD_1") (pintype "power_in"))
      (node (ref "LED36") (pin "1") (pinfunction "VDD_1") (pintype "power_in"))
      (node (ref "LED37") (pin "1") (pinfunction "VDD_1") (pintype "power_in"))
      (node (ref "LED38") (pin "1") (pinfunction "VDD_1") (pintype "power_in"))
      (node (ref "LED39") (pin "1") (pinfunction "VDD_1") (pintype "power_in"))
      (node (ref "LED4") (pin "1") (pinfunction "VDD_1") (pintype "power_in"))
      (node (ref "LED40") (pin "1") (pinfunction "VDD_1") (pintype "power_in"))
      (node (ref "LED41") (pin "1") (pinfunction "VDD_1") (pintype "power_in"))
      (node (ref "LED42") (pin "1") (pinfunction "VDD_1") (pintype "power_in"))
      (node (ref "LED43") (pin "1") (pinfunction "VDD_1") (pintype "power_in"))
      (node (ref "LED44") (pin "1") (pinfunction "VDD_1") (pintype "power_in"))
      (node (ref "LED45") (pin "1") (pinfunction "VDD_1") (pintype "power_in"))
      (node (ref "LED46") (pin "1") (pinfunction "VDD_1") (pintype "power_in"))
      (node (ref "LED47") (pin "1") (pinfunction "VDD_1") (pintype "power_in"))
      (node (ref "LED48") (pin "1") (pinfunction "VDD_1") (pintype "power_in"))
      (node (ref "LED49") (pin "1") (pinfunction "VDD_1") (pintype "power_in"))
      (node (ref "LED5") (pin "1") (pinfunction "VDD_1") (pintype "power_in"))
      (node (ref "LED50") (pin "1") (pinfunction "VDD_1") (pintype "power_in"))
      (node (ref "LED51") (pin "1") (pinfunction "VDD_1") (pintype "power_in"))
      (node (ref "LED52") (pin "1") (pinfunction "VDD_1") (pintype "power_in"))
      (node (ref "LED53") (pin "1") (pinfunction "VDD_1") (pintype "power_in"))
      (node (ref "LED54") (pin "1") (pinfunction "VDD_1") (pintype "power_in"))
      (node (ref "LED6") (pin "1") (pinfunction "VDD_1") (pintype "power_in"))
      (node (ref "LED7") (pin "1") (pinfunction "VDD_1") (pintype "power_in"))
      (node (ref "LED8") (pin "1") (pinfunction "VDD_1") (pintype "power_in"))
      (node (ref "LED9") (pin "1") (pinfunction "VDD_1") (pintype "power_in"))
      (node (ref "TP4") (pin "TP") (pinfunction "TP_TP") (pintype "input"))
      (node (ref "U2") (pin "1") (pinfunction "VIN_1") (pintype "passive"))
      (node (ref "U2") (pin "3") (pinfunction "EN_3") (pintype "passive"))
      (node (ref "U4") (pin "5") (pinfunction "VCC_5") (pintype "power_in"))
      (node (ref "U5") (pin "5") (pinfunction "VCC_5") (pintype "power_in"))
    )
    (net (code "4") (name "BT_~{DISABLE}") (class "Default")
      (node (ref "J2") (pin "B2") (pinfunction "B2_B2") (pintype "passive"))
      (node (ref "S56") (pin "2") (pinfunction "2_2") (pintype "passive"))
    )
    (net (code "5") (name "CM5_GPIO2") (class "Default")
      (node (ref "J2") (pin "A5") (pinfunction "A5_A5") (pintype "passive"))
      (node (ref "JP1") (pin "1") (pinfunction "1_1") (pintype "passive"))
    )
    (net (code "6") (name "CM5_GPIO3") (class "Default")
      (node (ref "J2") (pin "A6") (pinfunction "A6_A6") (pintype "passive"))
      (node (ref "JP2") (pin "1") (pinfunction "1_1") (pintype "passive"))
    )
    (net (code "7") (name "COL0") (class "Default")
      (node (ref "JP3") (pin "1") (pinfunction "1_1") (pintype "passive"))
      (node (ref "S1") (pin "P$2") (pinfunction "2_P$2") (pintype "passive"))
      (node (ref "S13") (pin "P$2") (pinfunction "2_P$2") (pintype "passive"))
      (node (ref "S25") (pin "P$2") (pinfunction "2_P$2") (pintype "passive"))
      (node (ref "S37") (pin "P$2") (pinfunction "2_P$2") (pintype "passive"))
      (node (ref "U1") (pin "14") (pinfunction "GPIO11_14") (pintype "bidirectional"))
    )
    (net (code "8") (name "COL1") (class "Default")
      (node (ref "S14") (pin "P$2") (pinfunction "2_P$2") (pintype "passive"))
      (node (ref "S2") (pin "P$2") (pinfunction "2_P$2") (pintype "passive"))
      (node (ref "S26") (pin "P$2") (pinfunction "2_P$2") (pintype "passive"))
      (node (ref "S38") (pin "P$2") (pinfunction "2_P$2") (pintype "passive"))
      (node (ref "U1") (pin "13") (pinfunction "GPIO10_13") (pintype "bidirectional"))
    )
    (net (code "9") (name "COL2") (class "Default")
      (node (ref "S15") (pin "P$2") (pinfunction "2_P$2") (pintype "passive"))
      (node (ref "S27") (pin "P$2") (pinfunction "2_P$2") (pintype "passive"))
      (node (ref "S3") (pin "P$2") (pinfunction "2_P$2") (pintype "passive"))
      (node (ref "S39") (pin "P$2") (pinfunction "2_P$2") (pintype "passive"))
      (node (ref "U1") (pin "12") (pinfunction "GPIO9_12") (pintype "bidirectional"))
    )
    (net (code "10") (name "COL3") (class "Default")
      (node (ref "S16") (pin "P$2") (pinfunction "2_P$2") (pintype "passive"))
      (node (ref "S28") (pin "P$2") (pinfunction "2_P$2") (pintype "passive"))
      (node (ref "S4") (pin "P$2") (pinfunction "2_P$2") (pintype "passive"))
      (node (ref "S40") (pin "P$2") (pinfunction "2_P$2") (pintype "passive"))
      (node (ref "S49") (pin "P$2") (pinfunction "2_P$2") (pintype "passive"))
      (node (ref "U1") (pin "11") (pinfunction "GPIO8_11") (pintype "bidirectional"))
    )
    (net (code "11") (name "COL4") (class "Default")
      (node (ref "S17") (pin "P$2") (pinfunction "2_P$2") (pintype "passive"))
      (node (ref "S29") (pin "P$2") (pinfunction "2_P$2") (pintype "passive"))
      (node (ref "S41") (pin "P$2") (pinfunction "2_P$2") (pintype "passive"))
      (node (ref "S5") (pin "P$2") (pinfunction "2_P$2") (pintype "passive"))
      (node (ref "S50") (pin "P$2") (pinfunction "2_P$2") (pintype "passive"))
      (node (ref "U1") (pin "9") (pinfunction "GPIO7_9") (pintype "bidirectional"))
    )
    (net (code "12") (name "COL5") (class "Default")
      (node (ref "S18") (pin "P$2") (pinfunction "2_P$2") (pintype "passive"))
      (node (ref "S30") (pin "P$2") (pinfunction "2_P$2") (pintype "passive"))
      (node (ref "S42") (pin "P$2") (pinfunction "2_P$2") (pintype "passive"))
      (node (ref "S51") (pin "P$2") (pinfunction "2_P$2") (pintype "passive"))
      (node (ref "S6") (pin "P$2") (pinfunction "2_P$2") (pintype "passive"))
      (node (ref "U1") (pin "8") (pinfunction "GPIO6_8") (pintype "bidirectional"))
    )
    (net (code "13") (name "COL6") (class "Default")
      (node (ref "S19") (pin "P$2") (pinfunction "2_P$2") (pintype "passive"))
      (node (ref "S31") (pin "P$2") (pinfunction "2_P$2") (pintype "passive"))
      (node (ref "S43") (pin "P$2") (pinfunction "2_P$2") (pintype "passive"))
      (node (ref "S52") (pin "P$2") (pinfunction "2_P$2") (pintype "passive"))
      (node (ref "S7") (pin "P$2") (pinfunction "2_P$2") (pintype "passive"))
      (node (ref "U1") (pin "7") (pinfunction "GPIO5_7") (pintype "bidirectional"))
    )
    (net (code "14") (name "COL7") (class "Default")
      (node (ref "S20") (pin "P$2") (pinfunction "2_P$2") (pintype "passive"))
      (node (ref "S32") (pin "P$2") (pinfunction "2_P$2") (pintype "passive"))
      (node (ref "S44") (pin "P$2") (pinfunction "2_P$2") (pintype "passive"))
      (node (ref "S53") (pin "P$2") (pinfunction "2_P$2") (pintype "passive"))
      (node (ref "S8") (pin "P$2") (pinfunction "2_P$2") (pintype "passive"))
      (node (ref "U1") (pin "6") (pinfunction "GPIO4_6") (pintype "bidirectional"))
    )
    (net (code "15") (name "COL8") (class "Default")
      (node (ref "S21") (pin "P$2") (pinfunction "2_P$2") (pintype "passive"))
      (node (ref "S33") (pin "P$2") (pinfunction "2_P$2") (pintype "passive"))
      (node (ref "S45") (pin "P$2") (pinfunction "2_P$2") (pintype "passive"))
      (node (ref "S54") (pin "P$2") (pinfunction "2_P$2") (pintype "passive"))
      (node (ref "S9") (pin "P$2") (pinfunction "2_P$2") (pintype "passive"))
      (node (ref "U1") (pin "5") (pinfunction "GPIO3_5") (pintype "bidirectional"))
    )
    (net (code "16") (name "COL9") (class "Default")
      (node (ref "S10") (pin "P$2") (pinfunction "2_P$2") (pintype "passive"))
      (node (ref "S22") (pin "P$2") (pinfunction "2_P$2") (pintype "passive"))
      (node (ref "S34") (pin "P$2") (pinfunction "2_P$2") (pintype "passive"))
      (node (ref "S46") (pin "P$2") (pinfunction "2_P$2") (pintype "passive"))
      (node (ref "U1") (pin "4") (pinfunction "GPIO2_4") (pintype "bidirectional"))
    )
    (net (code "17") (name "COL10") (class "Default")
      (node (ref "S11") (pin "P$2") (pinfunction "2_P$2") (pintype "passive"))
      (node (ref "S23") (pin "P$2") (pinfunction "2_P$2") (pintype "passive"))
      (node (ref "S35") (pin "P$2") (pinfunction "2_P$2") (pintype "passive"))
      (node (ref "S47") (pin "P$2") (pinfunction "2_P$2") (pintype "passive"))
      (node (ref "U1") (pin "3") (pinfunction "GPIO1_3") (pintype "bidirectional"))
    )
    (net (code "18") (name "COL11") (class "Default")
      (node (ref "S12") (pin "P$2") (pinfunction "2_P$2") (pintype "passive"))
      (node (ref "S24") (pin "P$2") (pinfunction "2_P$2") (pintype "passive"))
      (node (ref "S36") (pin "P$2") (pinfunction "2_P$2") (pintype "passive"))
      (node (ref "S48") (pin "P$2") (pinfunction "2_P$2") (pintype "passive"))
      (node (ref "U1") (pin "2") (pinfunction "GPIO0_2") (pintype "bidirectional"))
    )
    (net (code "19") (name "EEPROM_~{WP}") (class "Default")
      (node (ref "J2") (pin "B6") (pinfunction "B6_B6") (pintype "passive"))
      (node (ref "S60") (pin "2") (pinfunction "2_2") (pintype "passive"))
    )
    (net (code "20") (name "GND") (class "Default")
      (node (ref "BOOT") (pin "2") (pinfunction "2_2") (pintype "passive"))
      (node (ref "BOOT") (pin "3") (pinfunction "2_3") (pintype "passive"))
      (node (ref "C1") (pin "2") (pinfunction "2_2") (pintype "passive"))
      (node (ref "C10") (pin "2") (pinfunction "2_2") (pintype "passive"))
      (node (ref "C11") (pin "2") (pinfunction "2_2") (pintype "passive"))
      (node (ref "C12") (pin "2") (pinfunction "2_2") (pintype "passive"))
      (node (ref "C13") (pin "2") (pinfunction "2_2") (pintype "passive"))
      (node (ref "C14") (pin "1") (pinfunction "1_1") (pintype "passive"))
      (node (ref "C15") (pin "1") (pinfunction "1_1") (pintype "passive"))
      (node (ref "C16") (pin "2") (pinfunction "2_2") (pintype "passive"))
      (node (ref "C17") (pin "1") (pinfunction "1_1") (pintype "passive"))
      (node (ref "C18") (pin "1") (pinfunction "1_1") (pintype "passive"))
      (node (ref "C19") (pin "1") (pinfunction "1_1") (pintype "passive"))
      (node (ref "C2") (pin "2") (pinfunction "2_2") (pintype "passive"))
      (node (ref "C20") (pin "1") (pinfunction "1_1") (pintype "passive"))
      (node (ref "C21") (pin "1") (pinfunction "1_1") (pintype "passive"))
      (node (ref "C22") (pin "1") (pinfunction "1_1") (pintype "passive"))
      (node (ref "C23") (pin "1") (pinfunction "1_1") (pintype "passive"))
      (node (ref "C24") (pin "1") (pinfunction "1_1") (pintype "passive"))
      (node (ref "C25") (pin "1") (pinfunction "1_1") (pintype "passive"))
      (node (ref "C26") (pin "1") (pinfunction "1_1") (pintype "passive"))
      (node (ref "C27") (pin "1") (pinfunction "1_1") (pintype "passive"))
      (node (ref "C28") (pin "1") (pinfunction "1_1") (pintype "passive"))
      (node (ref "C29") (pin "1") (pinfunction "1_1") (pintype "passive"))
      (node (ref "C3") (pin "2") (pinfunction "2_2") (pintype "passive"))
      (node (ref "C30") (pin "1") (pinfunction "1_1") (pintype "passive"))
      (node (ref "C31") (pin "1") (pinfunction "1_1") (pintype "passive"))
      (node (ref "C32") (pin "1") (pinfunction "1_1") (pintype "passive"))
      (node (ref "C33") (pin "1") (pinfunction "1_1") (pintype "passive"))
      (node (ref "C34") (pin "1") (pinfunction "1_1") (pintype "passive"))
      (node (ref "C35") (pin "1") (pinfunction "1_1") (pintype "passive"))
      (node (ref "C36") (pin "1") (pinfunction "1_1") (pintype "passive"))
      (node (ref "C37") (pin "1") (pinfunction "1_1") (pintype "passive"))
      (node (ref "C38") (pin "1") (pinfunction "1_1") (pintype "passive"))
      (node (ref "C39") (pin "1") (pinfunction "1_1") (pintype "passive"))
      (node (ref "C4") (pin "2") (pinfunction "2_2") (pintype "passive"))
      (node (ref "C40") (pin "1") (pinfunction "1_1") (pintype "passive"))
      (node (ref "C41") (pin "1") (pinfunction "1_1") (pintype "passive"))
      (node (ref "C42") (pin "1") (pinfunction "1_1") (pintype "passive"))
      (node (ref "C43") (pin "1") (pinfunction "1_1") (pintype "passive"))
      (node (ref "C44") (pin "1") (pinfunction "1_1") (pintype "passive"))
      (node (ref "C45") (pin "1") (pinfunction "1_1") (pintype "passive"))
      (node (ref "C46") (pin "1") (pinfunction "1_1") (pintype "passive"))
      (node (ref "C47") (pin "1") (pinfunction "1_1") (pintype "passive"))
      (node (ref "C48") (pin "1") (pinfunction "1_1") (pintype "passive"))
      (node (ref "C49") (pin "1") (pinfunction "1_1") (pintype "passive"))
      (node (ref "C5") (pin "2") (pinfunction "2_2") (pintype "passive"))
      (node (ref "C50") (pin "1") (pinfunction "1_1") (pintype "passive"))
      (node (ref "C51") (pin "1") (pinfunction "1_1") (pintype "passive"))
      (node (ref "C52") (pin "1") (pinfunction "1_1") (pintype "passive"))
      (node (ref "C53") (pin "1") (pinfunction "1_1") (pintype "passive"))
      (node (ref "C54") (pin "1") (pinfunction "1_1") (pintype "passive"))
      (node (ref "C55") (pin "1") (pinfunction "1_1") (pintype "passive"))
      (node (ref "C56") (pin "1") (pinfunction "1_1") (pintype "passive"))
      (node (ref "C57") (pin "1") (pinfunction "1_1") (pintype "passive"))
      (node (ref "C58") (pin "1") (pinfunction "1_1") (pintype "passive"))
      (node (ref "C59") (pin "1") (pinfunction "1_1") (pintype "passive"))
      (node (ref "C6") (pin "2") (pinfunction "2_2") (pintype "passive"))
      (node (ref "C60") (pin "1") (pinfunction "1_1") (pintype "passive"))
      (node (ref "C61") (pin "1") (pinfunction "1_1") (pintype "passive"))
      (node (ref "C62") (pin "1") (pinfunction "1_1") (pintype "passive"))
      (node (ref "C63") (pin "1") (pinfunction "1_1") (pintype "passive"))
      (node (ref "C64") (pin "1") (pinfunction "1_1") (pintype "passive"))
      (node (ref "C65") (pin "1") (pinfunction "1_1") (pintype "passive"))
      (node (ref "C66") (pin "1") (pinfunction "1_1") (pintype "passive"))
      (node (ref "C67") (pin "1") (pinfunction "1_1") (pintype "passive"))
      (node (ref "C68") (pin "1") (pinfunction "1_1") (pintype "passive"))
      (node (ref "C69") (pin "1") (pinfunction "1_1") (pintype "passive"))
      (node (ref "C7") (pin "2") (pinfunction "2_2") (pintype "passive"))
      (node (ref "C70") (pin "1") (pinfunction "1_1") (pintype "passive"))
      (node (ref "C71") (pin "2") (pinfunction "2_2") (pintype "passive"))
      (node (ref "C72") (pin "2") (pinfunction "2_2") (pintype "passive"))
      (node (ref "C8") (pin "2") (pinfunction "2_2") (pintype "passive"))
      (node (ref "C9") (pin "2") (pinfunction "2_2") (pintype "passive"))
      (node (ref "J1") (pin "A1") (pinfunction "A1_A1") (pintype "passive"))
      (node (ref "J1") (pin "A4") (pinfunction "A4_A4") (pintype "passive"))
      (node (ref "J1") (pin "B4") (pinfunction "B4_B4") (pintype "passive"))
      (node (ref "J2") (pin "A1") (pinfunction "A1_A1") (pintype "passive"))
      (node (ref "J2") (pin "A2") (pinfunction "A2_A2") (pintype "passive"))
      (node (ref "J3") (pin "1") (pinfunction "1_1") (pintype "passive"))
      (node (ref "J3") (pin "11") (pinfunction "11_11") (pintype "passive"))
      (node (ref "J3") (pin "17") (pinfunction "17_17") (pintype "passive"))
      (node (ref "J3") (pin "18") (pinfunction "18_18") (pintype "passive"))
      (node (ref "J4") (pin "2") (pinfunction "2_2") (pintype "passive"))
      (node (ref "LED1") (pin "3") (pinfunction "GND_3") (pintype "power_in"))
      (node (ref "LED10") (pin "3") (pinfunction "GND_3") (pintype "power_in"))
      (node (ref "LED11") (pin "3") (pinfunction "GND_3") (pintype "power_in"))
      (node (ref "LED12") (pin "3") (pinfunction "GND_3") (pintype "power_in"))
      (node (ref "LED13") (pin "3") (pinfunction "GND_3") (pintype "power_in"))
      (node (ref "LED14") (pin "3") (pinfunction "GND_3") (pintype "power_in"))
      (node (ref "LED15") (pin "3") (pinfunction "GND_3") (pintype "power_in"))
      (node (ref "LED16") (pin "3") (pinfunction "GND_3") (pintype "power_in"))
      (node (ref "LED17") (pin "3") (pinfunction "GND_3") (pintype "power_in"))
      (node (ref "LED18") (pin "3") (pinfunction "GND_3") (pintype "power_in"))
      (node (ref "LED19") (pin "3") (pinfunction "GND_3") (pintype "power_in"))
      (node (ref "LED2") (pin "3") (pinfunction "GND_3") (pintype "power_in"))
      (node (ref "LED20") (pin "3") (pinfunction "GND_3") (pintype "power_in"))
      (node (ref "LED21") (pin "3") (pinfunction "GND_3") (pintype "power_in"))
      (node (ref "LED22") (pin "3") (pinfunction "GND_3") (pintype "power_in"))
      (node (ref "LED23") (pin "3") (pinfunction "GND_3") (pintype "power_in"))
      (node (ref "LED24") (pin "3") (pinfunction "GND_3") (pintype "power_in"))
      (node (ref "LED25") (pin "3") (pinfunction "GND_3") (pintype "power_in"))
      (node (ref "LED26") (pin "3") (pinfunction "GND_3") (pintype "power_in"))
      (node (ref "LED27") (pin "3") (pinfunction "GND_3") (pintype "power_in"))
      (node (ref "LED28") (pin "3") (pinfunction "GND_3") (pintype "power_in"))
      (node (ref "LED29") (pin "3") (pinfunction "GND_3") (pintype "power_in"))
      (node (ref "LED3") (pin "3") (pinfunction "GND_3") (pintype "power_in"))
      (node (ref "LED30") (pin "3") (pinfunction "GND_3") (pintype "power_in"))
      (node (ref "LED31") (pin "3") (pinfunction "GND_3") (pintype "power_in"))
      (node (ref "LED32") (pin "3") (pinfunction "GND_3") (pintype "power_in"))
      (node (ref "LED33") (pin "3") (pinfunction "GND_3") (pintype "power_in"))
      (node (ref "LED34") (pin "3") (pinfunction "GND_3") (pintype "power_in"))
      (node (ref "LED35") (pin "3") (pinfunction "GND_3") (pintype "power_in"))
      (node (ref "LED36") (pin "3") (pinfunction "GND_3") (pintype "power_in"))
      (node (ref "LED37") (pin "3") (pinfunction "GND_3") (pintype "power_in"))
      (node (ref "LED38") (pin "3") (pinfunction "GND_3") (pintype "power_in"))
      (node (ref "LED39") (pin "3") (pinfunction "GND_3") (pintype "power_in"))
      (node (ref "LED4") (pin "3") (pinfunction "GND_3") (pintype "power_in"))
      (node (ref "LED40") (pin "3") (pinfunction "GND_3") (pintype "power_in"))
      (node (ref "LED41") (pin "3") (pinfunction "GND_3") (pintype "power_in"))
      (node (ref "LED42") (pin "3") (pinfunction "GND_3") (pintype "power_in"))
      (node (ref "LED43") (pin "3") (pinfunction "GND_3") (pintype "power_in"))
      (node (ref "LED44") (pin "3") (pinfunction "GND_3") (pintype "power_in"))
      (node (ref "LED45") (pin "3") (pinfunction "GND_3") (pintype "power_in"))
      (node (ref "LED46") (pin "3") (pinfunction "GND_3") (pintype "power_in"))
      (node (ref "LED47") (pin "3") (pinfunction "GND_3") (pintype "power_in"))
      (node (ref "LED48") (pin "3") (pinfunction "GND_3") (pintype "power_in"))
      (node (ref "LED49") (pin "3") (pinfunction "GND_3") (pintype "power_in"))
      (node (ref "LED5") (pin "3") (pinfunction "GND_3") (pintype "power_in"))
      (node (ref "LED50") (pin "3") (pinfunction "GND_3") (pintype "power_in"))
      (node (ref "LED51") (pin "3") (pinfunction "GND_3") (pintype "power_in"))
      (node (ref "LED52") (pin "3") (pinfunction "GND_3") (pintype "power_in"))
      (node (ref "LED53") (pin "3") (pinfunction "GND_3") (pintype "power_in"))
      (node (ref "LED54") (pin "3") (pinfunction "GND_3") (pintype "power_in"))
      (node (ref "LED6") (pin "3") (pinfunction "GND_3") (pintype "power_in"))
      (node (ref "LED7") (pin "3") (pinfunction "GND_3") (pintype "power_in"))
      (node (ref "LED8") (pin "3") (pinfunction "GND_3") (pintype "power_in"))
      (node (ref "LED9") (pin "3") (pinfunction "GND_3") (pintype "power_in"))
      (node (ref "R11") (pin "1") (pinfunction "1_1") (pintype "passive"))
      (node (ref "R7") (pin "1") (pinfunction "1_1") (pintype "passive"))
      (node (ref "R8") (pin "1") (pinfunction "1_1") (pintype "passive"))
      (node (ref "RESET") (pin "2") (pinfunction "2_2") (pintype "passive"))
      (node (ref "RESET") (pin "3") (pinfunction "2_3") (pintype "passive"))
      (node (ref "S55") (pin "1") (pinfunction "1_1") (pintype "passive"))
      (node (ref "S56") (pin "1") (pinfunction "1_1") (pintype "passive"))
      (node (ref "S57") (pin "3") (pinfunction "3_3") (pintype "passive"))
      (node (ref "S58") (pin "3") (pinfunction "3_3") (pintype "passive"))
      (node (ref "S59") (pin "3") (pinfunction "3_3") (pintype "passive"))
      (node (ref "S60") (pin "3") (pinfunction "3_3") (pintype "passive"))
      (node (ref "S61") (pin "3") (pinfunction "2_3") (pintype "passive"))
      (node (ref "S61") (pin "4") (pinfunction "2_4") (pintype "passive"))
      (node (ref "TP13") (pin "TP") (pinfunction "TP_TP") (pintype "input"))
      (node (ref "TP5") (pin "TP") (pinfunction "TP_TP") (pintype "input"))
      (node (ref "TP6") (pin "TP") (pinfunction "TP_TP") (pintype "input"))
      (node (ref "TP7") (pin "TP") (pinfunction "TP_TP") (pintype "input"))
      (node (ref "U$1") (pin "P$2") (pinfunction "C_P$2") (pintype "passive"))
      (node (ref "U1") (pin "19") (pinfunction "TESTEN_19") (pintype "passive"))
      (node (ref "U1") (pin "57") (pinfunction "GND_57") (pintype "power_in"))
      (node (ref "U2") (pin "2") (pinfunction "GND_2") (pintype "passive"))
      (node (ref "U3") (pin "4") (pinfunction "GND_4") (pintype "power_in"))
      (node (ref "U4") (pin "1") (pinfunction "~{OE}_1") (pintype "input"))
      (node (ref "U4") (pin "3") (pinfunction "GND_3") (pintype "power_in"))
      (node (ref "U5") (pin "1") (pinfunction "~{OE}_1") (pintype "input"))
      (node (ref "U5") (pin "3") (pinfunction "GND_3") (pintype "power_in"))
      (node (ref "Y1") (pin "2") (pinfunction "GND_2") (pintype "power_in"))
      (node (ref "Y1") (pin "4") (pinfunction "GND_4") (pintype "power_in"))
    )
    (net (code "21") (name "LED_~{ACTIVITY}") (class "Default")
      (node (ref "J1") (pin "B1") (pinfunction "B1_B1") (pintype "passive"))
      (node (ref "R9") (pin "1") (pinfunction "1_1") (pintype "passive"))
    )
    (net (code "22") (name "LED_~{PWR}") (class "Default")
      (node (ref "J1") (pin "B2") (pinfunction "B2_B2") (pintype "passive"))
      (node (ref "U4") (pin "2") (pinfunction "A_2") (pintype "input"))
    )
    (net (code "23") (name "MISO") (class "Default")
      (node (ref "J4") (pin "11") (pinfunction "11_11") (pintype "passive"))
      (node (ref "U1") (pin "40") (pinfunction "GPIO28/ADC2_40") (pintype "bidirectional"))
    )
    (net (code "24") (name "MOSI") (class "Default")
      (node (ref "J3") (pin "5") (pinfunction "5_5") (pintype "passive"))
      (node (ref "J4") (pin "8") (pinfunction "8_8") (pintype "passive"))
      (node (ref "U1") (pin "39") (pinfunction "GPIO27/ADC1_39") (pintype "bidirectional"))
    )
    (net (code "25") (name "Net-(C15-Pad2)") (class "Default")
      (node (ref "C15") (pin "2") (pinfunction "2_2") (pintype "passive"))
      (node (ref "R1") (pin "1") (pinfunction "1_1") (pintype "passive"))
      (node (ref "Y1") (pin "3") (pinfunction "3_3") (pintype "passive"))
    )
    (net (code "26") (name "Net-(C71-Pad1)") (class "Default")
      (node (ref "C71") (pin "1") (pinfunction "1_1") (pintype "passive"))
      (node (ref "J3") (pin "2") (pinfunction "2_2") (pintype "passive"))
    )
    (net (code "27") (name "Net-(C72-Pad1)") (class "Default")
      (node (ref "C72") (pin "1") (pinfunction "1_1") (pintype "passive"))
      (node (ref "J3") (pin "3") (pinfunction "3_3") (pintype "passive"))
    )
    (net (code "28") (name "Net-(C73-Pad1)") (class "Default")
      (node (ref "C73") (pin "1") (pinfunction "1_1") (pintype "passive"))
      (node (ref "J3") (pin "14") (pinfunction "14_14") (pintype "passive"))
    )
    (net (code "29") (name "Net-(C73-Pad2)") (class "Default")
      (node (ref "C73") (pin "2") (pinfunction "2_2") (pintype "passive"))
      (node (ref "J3") (pin "13") (pinfunction "13_13") (pintype "passive"))
    )
    (net (code "30") (name "Net-(C74-Pad1)") (class "Default")
      (node (ref "C74") (pin "1") (pinfunction "1_1") (pintype "passive"))
      (node (ref "J3") (pin "16") (pinfunction "16_16") (pintype "passive"))
    )
    (net (code "31") (name "Net-(C74-Pad2)") (class "Default")
      (node (ref "C74") (pin "2") (pinfunction "2_2") (pintype "passive"))
      (node (ref "J3") (pin "15") (pinfunction "15_15") (pintype "passive"))
    )
    (net (code "32") (name "Net-(D58-PadC)") (class "Default")
      (node (ref "D58") (pin "C") (pinfunction "C_C") (pintype "passive"))
      (node (ref "R10") (pin "2") (pinfunction "2_2") (pintype "passive"))
    )
    (net (code "33") (name "Net-(D59-PadC)") (class "Default")
      (node (ref "D59") (pin "C") (pinfunction "C_C") (pintype "passive"))
      (node (ref "R9") (pin "2") (pinfunction "2_2") (pintype "passive"))
    )
    (net (code "34") (name "Net-(J3-Pad4)") (class "Default")
      (node (ref "J3") (pin "4") (pinfunction "4_4") (pintype "passive"))
      (node (ref "R7") (pin "2") (pinfunction "2_2") (pintype "passive"))
    )
    (net (code "35") (name "Net-(LED1-DOUT)") (class "Default")
      (node (ref "LED1") (pin "2") (pinfunction "DOUT_2") (pintype "output"))
      (node (ref "LED2") (pin "4") (pinfunction "DIN_4") (pintype "input"))
    )
    (net (code "36") (name "Net-(LED2-DOUT)") (class "Default")
      (node (ref "LED2") (pin "2") (pinfunction "DOUT_2") (pintype "output"))
      (node (ref "LED3") (pin "4") (pinfunction "DIN_4") (pintype "input"))
    )
    (net (code "37") (name "Net-(LED3-DOUT)") (class "Default")
      (node (ref "LED3") (pin "2") (pinfunction "DOUT_2") (pintype "output"))
      (node (ref "LED4") (pin "4") (pinfunction "DIN_4") (pintype "input"))
    )
    (net (code "38") (name "Net-(LED4-DOUT)") (class "Default")
      (node (ref "LED4") (pin "2") (pinfunction "DOUT_2") (pintype "output"))
      (node (ref "LED5") (pin "4") (pinfunction "DIN_4") (pintype "input"))
    )
    (net (code "39") (name "Net-(LED5-DOUT)") (class "Default")
      (node (ref "LED5") (pin "2") (pinfunction "DOUT_2") (pintype "output"))
      (node (ref "LED6") (pin "4") (pinfunction "DIN_4") (pintype "input"))
    )
    (net (code "40") (name "Net-(LED6-DOUT)") (class "Default")
      (node (ref "LED6") (pin "2") (pinfunction "DOUT_2") (pintype "output"))
      (node (ref "LED7") (pin "4") (pinfunction "DIN_4") (pintype "input"))
    )
    (net (code "41") (name "Net-(LED7-DOUT)") (class "Default")
      (node (ref "LED7") (pin "2") (pinfunction "DOUT_2") (pintype "output"))
      (node (ref "LED8") (pin "4") (pinfunction "DIN_4") (pintype "input"))
    )
    (net (code "42") (name "Net-(LED8-DOUT)") (class "Default")
      (node (ref "LED8") (pin "2") (pinfunction "DOUT_2") (pintype "output"))
      (node (ref "LED9") (pin "4") (pinfunction "DIN_4") (pintype "input"))
    )
    (net (code "43") (name "Net-(LED10-DIN)") (class "Default")
      (node (ref "LED10") (pin "4") (pinfunction "DIN_4") (pintype "input"))
      (node (ref "LED9") (pin "2") (pinfunction "DOUT_2") (pintype "output"))
    )
    (net (code "44") (name "Net-(LED10-DOUT)") (class "Default")
      (node (ref "LED10") (pin "2") (pinfunction "DOUT_2") (pintype "output"))
      (node (ref "LED11") (pin "4") (pinfunction "DIN_4") (pintype "input"))
    )
    (net (code "45") (name "Net-(LED11-DOUT)") (class "Default")
      (node (ref "LED11") (pin "2") (pinfunction "DOUT_2") (pintype "output"))
      (node (ref "LED12") (pin "4") (pinfunction "DIN_4") (pintype "input"))
    )
    (net (code "46") (name "Net-(LED12-DOUT)") (class "Default")
      (node (ref "LED12") (pin "2") (pinfunction "DOUT_2") (pintype "output"))
      (node (ref "LED13") (pin "4") (pinfunction "DIN_4") (pintype "input"))
    )
    (net (code "47") (name "Net-(LED13-DOUT)") (class "Default")
      (node (ref "LED13") (pin "2") (pinfunction "DOUT_2") (pintype "output"))
      (node (ref "LED14") (pin "4") (pinfunction "DIN_4") (pintype "input"))
    )
    (net (code "48") (name "Net-(LED14-DOUT)") (class "Default")
      (node (ref "LED14") (pin "2") (pinfunction "DOUT_2") (pintype "output"))
      (node (ref "LED15") (pin "4") (pinfunction "DIN_4") (pintype "input"))
    )
    (net (code "49") (name "Net-(LED15-DOUT)") (class "Default")
      (node (ref "LED15") (pin "2") (pinfunction "DOUT_2") (pintype "output"))
      (node (ref "LED16") (pin "4") (pinfunction "DIN_4") (pintype "input"))
    )
    (net (code "50") (name "Net-(LED16-DOUT)") (class "Default")
      (node (ref "LED16") (pin "2") (pinfunction "DOUT_2") (pintype "output"))
      (node (ref "LED17") (pin "4") (pinfunction "DIN_4") (pintype "input"))
    )
    (net (code "51") (name "Net-(LED17-DOUT)") (class "Default")
      (node (ref "LED17") (pin "2") (pinfunction "DOUT_2") (pintype "output"))
      (node (ref "LED18") (pin "4") (pinfunction "DIN_4") (pintype "input"))
    )
    (net (code "52") (name "Net-(LED18-DOUT)") (class "Default")
      (node (ref "LED18") (pin "2") (pinfunction "DOUT_2") (pintype "output"))
      (node (ref "LED19") (pin "4") (pinfunction "DIN_4") (pintype "input"))
    )
    (net (code "53") (name "Net-(LED19-DOUT)") (class "Default")
      (node (ref "LED19") (pin "2") (pinfunction "DOUT_2") (pintype "output"))
      (node (ref "LED20") (pin "4") (pinfunction "DIN_4") (pintype "input"))
    )
    (net (code "54") (name "Net-(LED20-DOUT)") (class "Default")
      (node (ref "LED20") (pin "2") (pinfunction "DOUT_2") (pintype "output"))
      (node (ref "LED21") (pin "4") (pinfunction "DIN_4") (pintype "input"))
    )
    (net (code "55") (name "Net-(LED21-DOUT)") (class "Default")
      (node (ref "LED21") (pin "2") (pinfunction "DOUT_2") (pintype "output"))
      (node (ref "LED22") (pin "4") (pinfunction "DIN_4") (pintype "input"))
    )
    (net (code "56") (name "Net-(LED22-DOUT)") (class "Default")
      (node (ref "LED22") (pin "2") (pinfunction "DOUT_2") (pintype "output"))
      (node (ref "LED23") (pin "4") (pinfunction "DIN_4") (pintype "input"))
    )
    (net (code "57") (name "Net-(LED23-DOUT)") (class "Default")
      (node (ref "LED23") (pin "2") (pinfunction "DOUT_2") (pintype "output"))
      (node (ref "LED24") (pin "4") (pinfunction "DIN_4") (pintype "input"))
    )
    (net (code "58") (name "Net-(LED24-DOUT)") (class "Default")
      (node (ref "LED24") (pin "2") (pinfunction "DOUT_2") (pintype "output"))
      (node (ref "LED25") (pin "4") (pinfunction "DIN_4") (pintype "input"))
    )
    (net (code "59") (name "Net-(LED25-DOUT)") (class "Default")
      (node (ref "LED25") (pin "2") (pinfunction "DOUT_2") (pintype "output"))
      (node (ref "LED26") (pin "4") (pinfunction "DIN_4") (pintype "input"))
    )
    (net (code "60") (name "Net-(LED26-DOUT)") (class "Default")
      (node (ref "LED26") (pin "2") (pinfunction "DOUT_2") (pintype "output"))
      (node (ref "LED27") (pin "4") (pinfunction "DIN_4") (pintype "input"))
    )
    (net (code "61") (name "Net-(LED27-DOUT)") (class "Default")
      (node (ref "LED27") (pin "2") (pinfunction "DOUT_2") (pintype "output"))
      (node (ref "LED28") (pin "4") (pinfunction "DIN_4") (pintype "input"))
    )
    (net (code "62") (name "Net-(LED28-DOUT)") (class "Default")
      (node (ref "LED28") (pin "2") (pinfunction "DOUT_2") (pintype "output"))
      (node (ref "LED29") (pin "4") (pinfunction "DIN_4") (pintype "input"))
    )
    (net (code "63") (name "Net-(LED29-DOUT)") (class "Default")
      (node (ref "LED29") (pin "2") (pinfunction "DOUT_2") (pintype "output"))
      (node (ref "LED30") (pin "4") (pinfunction "DIN_4") (pintype "input"))
    )
    (net (code "64") (name "Net-(LED30-DOUT)") (class "Default")
      (node (ref "LED30") (pin "2") (pinfunction "DOUT_2") (pintype "output"))
      (node (ref "LED31") (pin "4") (pinfunction "DIN_4") (pintype "input"))
    )
    (net (code "65") (name "Net-(LED31-DOUT)") (class "Default")
      (node (ref "LED31") (pin "2") (pinfunction "DOUT_2") (pintype "output"))
      (node (ref "LED32") (pin "4") (pinfunction "DIN_4") (pintype "input"))
    )
    (net (code "66") (name "Net-(LED32-DOUT)") (class "Default")
      (node (ref "LED32") (pin "2") (pinfunction "DOUT_2") (pintype "output"))
      (node (ref "LED33") (pin "4") (pinfunction "DIN_4") (pintype "input"))
    )
    (net (code "67") (name "Net-(LED33-DOUT)") (class "Default")
      (node (ref "LED33") (pin "2") (pinfunction "DOUT_2") (pintype "output"))
      (node (ref "LED34") (pin "4") (pinfunction "DIN_4") (pintype "input"))
    )
    (net (code "68") (name "Net-(LED34-DOUT)") (class "Default")
      (node (ref "LED34") (pin "2") (pinfunction "DOUT_2") (pintype "output"))
      (node (ref "LED35") (pin "4") (pinfunction "DIN_4") (pintype "input"))
    )
    (net (code "69") (name "Net-(LED35-DOUT)") (class "Default")
      (node (ref "LED35") (pin "2") (pinfunction "DOUT_2") (pintype "output"))
      (node (ref "LED36") (pin "4") (pinfunction "DIN_4") (pintype "input"))
    )
    (net (code "70") (name "Net-(LED36-DOUT)") (class "Default")
      (node (ref "LED36") (pin "2") (pinfunction "DOUT_2") (pintype "output"))
      (node (ref "LED37") (pin "4") (pinfunction "DIN_4") (pintype "input"))
    )
    (net (code "71") (name "Net-(LED37-DOUT)") (class "Default")
      (node (ref "LED37") (pin "2") (pinfunction "DOUT_2") (pintype "output"))
      (node (ref "LED38") (pin "4") (pinfunction "DIN_4") (pintype "input"))
    )
    (net (code "72") (name "Net-(LED38-DOUT)") (class "Default")
      (node (ref "LED38") (pin "2") (pinfunction "DOUT_2") (pintype "output"))
      (node (ref "LED39") (pin "4") (pinfunction "DIN_4") (pintype "input"))
    )
    (net (code "73") (name "Net-(LED39-DOUT)") (class "Default")
      (node (ref "LED39") (pin "2") (pinfunction "DOUT_2") (pintype "output"))
      (node (ref "LED40") (pin "4") (pinfunction "DIN_4") (pintype "input"))
    )
    (net (code "74") (name "Net-(LED40-DOUT)") (class "Default")
      (node (ref "LED40") (pin "2") (pinfunction "DOUT_2") (pintype "output"))
      (node (ref "LED41") (pin "4") (pinfunction "DIN_4") (pintype "input"))
    )
    (net (code "75") (name "Net-(LED41-DOUT)") (class "Default")
      (node (ref "LED41") (pin "2") (pinfunction "DOUT_2") (pintype "output"))
      (node (ref "LED42") (pin "4") (pinfunction "DIN_4") (pintype "input"))
    )
    (net (code "76") (name "Net-(LED42-DOUT)") (class "Default")
      (node (ref "LED42") (pin "2") (pinfunction "DOUT_2") (pintype "output"))
      (node (ref "LED43") (pin "4") (pinfunction "DIN_4") (pintype "input"))
    )
    (net (code "77") (name "Net-(LED43-DOUT)") (class "Default")
      (node (ref "LED43") (pin "2") (pinfunction "DOUT_2") (pintype "output"))
      (node (ref "LED44") (pin "4") (pinfunction "DIN_4") (pintype "input"))
    )
    (net (code "78") (name "Net-(LED44-DOUT)") (class "Default")
      (node (ref "LED44") (pin "2") (pinfunction "DOUT_2") (pintype "output"))
      (node (ref "LED45") (pin "4") (pinfunction "DIN_4") (pintype "input"))
    )
    (net (code "79") (name "Net-(LED45-DOUT)") (class "Default")
      (node (ref "LED45") (pin "2") (pinfunction "DOUT_2") (pintype "output"))
      (node (ref "LED46") (pin "4") (pinfunction "DIN_4") (pintype "input"))
    )
    (net (code "80") (name "Net-(LED46-DOUT)") (class "Default")
      (node (ref "LED46") (pin "2") (pinfunction "DOUT_2") (pintype "output"))
      (node (ref "LED47") (pin "4") (pinfunction "DIN_4") (pintype "input"))
    )
    (net (code "81") (name "Net-(LED47-DOUT)") (class "Default")
      (node (ref "LED47") (pin "2") (pinfunction "DOUT_2") (pintype "output"))
      (node (ref "LED48") (pin "4") (pinfunction "DIN_4") (pintype "input"))
    )
    (net (code "82") (name "Net-(LED48-DOUT)") (class "Default")
      (node (ref "LED48") (pin "2") (pinfunction "DOUT_2") (pintype "output"))
      (node (ref "LED49") (pin "4") (pinfunction "DIN_4") (pintype "input"))
    )
    (net (code "83") (name "Net-(LED49-DOUT)") (class "Default")
      (node (ref "LED49") (pin "2") (pinfunction "DOUT_2") (pintype "output"))
      (node (ref "LED50") (pin "4") (pinfunction "DIN_4") (pintype "input"))
    )
    (net (code "84") (name "Net-(LED50-DOUT)") (class "Default")
      (node (ref "LED50") (pin "2") (pinfunction "DOUT_2") (pintype "output"))
      (node (ref "LED51") (pin "4") (pinfunction "DIN_4") (pintype "input"))
    )
    (net (code "85") (name "Net-(LED51-DOUT)") (class "Default")
      (node (ref "LED51") (pin "2") (pinfunction "DOUT_2") (pintype "output"))
      (node (ref "LED52") (pin "4") (pinfunction "DIN_4") (pintype "input"))
    )
    (net (code "86") (name "Net-(LED52-DOUT)") (class "Default")
      (node (ref "LED52") (pin "2") (pinfunction "DOUT_2") (pintype "output"))
      (node (ref "LED53") (pin "4") (pinfunction "DIN_4") (pintype "input"))
    )
    (net (code "87") (name "Net-(LED53-DOUT)") (class "Default")
      (node (ref "LED53") (pin "2") (pinfunction "DOUT_2") (pintype "output"))
      (node (ref "LED54") (pin "4") (pinfunction "DIN_4") (pintype "input"))
    )
    (net (code "88") (name "Net-(S1-1)") (class "Default")
      (node (ref "D1") (pin "A") (pinfunction "A_A") (pintype "passive"))
      (node (ref "S1") (pin "P$1") (pinfunction "1_P$1") (pintype "passive"))
    )
    (net (code "89") (name "Net-(S2-1)") (class "Default")
      (node (ref "D2") (pin "A") (pinfunction "A_A") (pintype "passive"))
      (node (ref "S2") (pin "P$1") (pinfunction "1_P$1") (pintype "passive"))
    )
    (net (code "90") (name "Net-(S3-1)") (class "Default")
      (node (ref "D3") (pin "A") (pinfunction "A_A") (pintype "passive"))
      (node (ref "S3") (pin "P$1") (pinfunction "1_P$1") (pintype "passive"))
    )
    (net (code "91") (name "Net-(S4-1)") (class "Default")
      (node (ref "D4") (pin "A") (pinfunction "A_A") (pintype "passive"))
      (node (ref "S4") (pin "P$1") (pinfunction "1_P$1") (pintype "passive"))
    )
    (net (code "92") (name "Net-(S5-1)") (class "Default")
      (node (ref "D5") (pin "A") (pinfunction "A_A") (pintype "passive"))
      (node (ref "S5") (pin "P$1") (pinfunction "1_P$1") (pintype "passive"))
    )
    (net (code "93") (name "Net-(S6-1)") (class "Default")
      (node (ref "D6") (pin "A") (pinfunction "A_A") (pintype "passive"))
      (node (ref "S6") (pin "P$1") (pinfunction "1_P$1") (pintype "passive"))
    )
    (net (code "94") (name "Net-(S7-1)") (class "Default")
      (node (ref "D7") (pin "A") (pinfunction "A_A") (pintype "passive"))
      (node (ref "S7") (pin "P$1") (pinfunction "1_P$1") (pintype "passive"))
    )
    (net (code "95") (name "Net-(S8-1)") (class "Default")
      (node (ref "D8") (pin "A") (pinfunction "A_A") (pintype "passive"))
      (node (ref "S8") (pin "P$1") (pinfunction "1_P$1") (pintype "passive"))
    )
    (net (code "96") (name "Net-(S9-1)") (class "Default")
      (node (ref "D9") (pin "A") (pinfunction "A_A") (pintype "passive"))
      (node (ref "S9") (pin "P$1") (pinfunction "1_P$1") (pintype "passive"))
    )
    (net (code "97") (name "Net-(S10-1)") (class "Default")
      (node (ref "D10") (pin "A") (pinfunction "A_A") (pintype "passive"))
      (node (ref "S10") (pin "P$1") (pinfunction "1_P$1") (pintype "passive"))
    )
    (net (code "98") (name "Net-(S11-1)") (class "Default")
      (node (ref "D11") (pin "A") (pinfunction "A_A") (pintype "passive"))
      (node (ref "S11") (pin "P$1") (pinfunction "1_P$1") (pintype "passive"))
    )
    (net (code "99") (name "Net-(S12-1)") (class "Default")
      (node (ref "D12") (pin "A") (pinfunction "A_A") (pintype "passive"))
      (node (ref "S12") (pin "P$1") (pinfunction "1_P$1") (pintype "passive"))
    )
    (net (code "100") (name "Net-(S13-1)") (class "Default")
      (node (ref "D13") (pin "A") (pinfunction "A_A") (pintype "passive"))
      (node (ref "S13") (pin "P$1") (pinfunction "1_P$1") (pintype "passive"))
    )
    (net (code "101") (name "Net-(S14-1)") (class "Default")
      (node (ref "D14") (pin "A") (pinfunction "A_A") (pintype "passive"))
      (node (ref "S14") (pin "P$1") (pinfunction "1_P$1") (pintype "passive"))
    )
    (net (code "102") (name "Net-(S15-1)") (class "Default")
      (node (ref "D15") (pin "A") (pinfunction "A_A") (pintype "passive"))
      (node (ref "S15") (pin "P$1") (pinfunction "1_P$1") (pintype "passive"))
    )
    (net (code "103") (name "Net-(S16-1)") (class "Default")
      (node (ref "D16") (pin "A") (pinfunction "A_A") (pintype "passive"))
      (node (ref "S16") (pin "P$1") (pinfunction "1_P$1") (pintype "passive"))
    )
    (net (code "104") (name "Net-(S17-1)") (class "Default")
      (node (ref "D17") (pin "A") (pinfunction "A_A") (pintype "passive"))
      (node (ref "S17") (pin "P$1") (pinfunction "1_P$1") (pintype "passive"))
    )
    (net (code "105") (name "Net-(S18-1)") (class "Default")
      (node (ref "D18") (pin "A") (pinfunction "A_A") (pintype "passive"))
      (node (ref "S18") (pin "P$1") (pinfunction "1_P$1") (pintype "passive"))
    )
    (net (code "106") (name "Net-(S19-1)") (class "Default")
      (node (ref "D19") (pin "A") (pinfunction "A_A") (pintype "passive"))
      (node (ref "S19") (pin "P$1") (pinfunction "1_P$1") (pintype "passive"))
    )
    (net (code "107") (name "Net-(S20-1)") (class "Default")
      (node (ref "D20") (pin "A") (pinfunction "A_A") (pintype "passive"))
      (node (ref "S20") (pin "P$1") (pinfunction "1_P$1") (pintype "passive"))
    )
    (net (code "108") (name "Net-(S21-1)") (class "Default")
      (node (ref "D21") (pin "A") (pinfunction "A_A") (pintype "passive"))
      (node (ref "S21") (pin "P$1") (pinfunction "1_P$1") (pintype "passive"))
    )
    (net (code "109") (name "Net-(S22-1)") (class "Default")
      (node (ref "D22") (pin "A") (pinfunction "A_A") (pintype "passive"))
      (node (ref "S22") (pin "P$1") (pinfunction "1_P$1") (pintype "passive"))
    )
    (net (code "110") (name "Net-(S23-1)") (class "Default")
      (node (ref "D23") (pin "A") (pinfunction "A_A") (pintype "passive"))
      (node (ref "S23") (pin "P$1") (pinfunction "1_P$1") (pintype "passive"))
    )
    (net (code "111") (name "Net-(S24-1)") (class "Default")
      (node (ref "D24") (pin "A") (pinfunction "A_A") (pintype "passive"))
      (node (ref "S24") (pin "P$1") (pinfunction "1_P$1") (pintype "passive"))
    )
    (net (code "112") (name "Net-(S25-1)") (class "Default")
      (node (ref "D25") (pin "A") (pinfunction "A_A") (pintype "passive"))
      (node (ref "S25") (pin "P$1") (pinfunction "1_P$1") (pintype "passive"))
    )
    (net (code "113") (name "Net-(S26-1)") (class "Default")
      (node (ref "D26") (pin "A") (pinfunction "A_A") (pintype "passive"))
      (node (ref "S26") (pin "P$1") (pinfunction "1_P$1") (pintype "passive"))
    )
    (net (code "114") (name "Net-(S27-1)") (class "Default")
      (node (ref "D27") (pin "A") (pinfunction "A_A") (pintype "passive"))
      (node (ref "S27") (pin "P$1") (pinfunction "1_P$1") (pintype "passive"))
    )
    (net (code "115") (name "Net-(S28-1)") (class "Default")
      (node (ref "D28") (pin "A") (pinfunction "A_A") (pintype "passive"))
      (node (ref "S28") (pin "P$1") (pinfunction "1_P$1") (pintype "passive"))
    )
    (net (code "116") (name "Net-(S29-1)") (class "Default")
      (node (ref "D29") (pin "A") (pinfunction "A_A") (pintype "passive"))
      (node (ref "S29") (pin "P$1") (pinfunction "1_P$1") (pintype "passive"))
    )
    (net (code "117") (name "Net-(S30-1)") (class "Default")
      (node (ref "D30") (pin "A") (pinfunction "A_A") (pintype "passive"))
      (node (ref "S30") (pin "P$1") (pinfunction "1_P$1") (pintype "passive"))
    )
    (net (code "118") (name "Net-(S31-1)") (class "Default")
      (node (ref "D31") (pin "A") (pinfunction "A_A") (pintype "passive"))
      (node (ref "S31") (pin "P$1") (pinfunction "1_P$1") (pintype "passive"))
    )
    (net (code "119") (name "Net-(S32-1)") (class "Default")
      (node (ref "D32") (pin "A") (pinfunction "A_A") (pintype "passive"))
      (node (ref "S32") (pin "P$1") (pinfunction "1_P$1") (pintype "passive"))
    )
    (net (code "120") (name "Net-(S33-1)") (class "Default")
      (node (ref "D33") (pin "A") (pinfunction "A_A") (pintype "passive"))
      (node (ref "S33") (pin "P$1") (pinfunction "1_P$1") (pintype "passive"))
    )
    (net (code "121") (name "Net-(S34-1)") (class "Default")
      (node (ref "D34") (pin "A") (pinfunction "A_A") (pintype "passive"))
      (node (ref "S34") (pin "P$1") (pinfunction "1_P$1") (pintype "passive"))
    )
    (net (code "122") (name "Net-(S35-1)") (class "Default")
      (node (ref "D35") (pin "A") (pinfunction "A_A") (pintype "passive"))
      (node (ref "S35") (pin "P$1") (pinfunction "1_P$1") (pintype "passive"))
    )
    (net (code "123") (name "Net-(S36-1)") (class "Default")
      (node (ref "D36") (pin "A") (pinfunction "A_A") (pintype "passive"))
      (node (ref "S36") (pin "P$1") (pinfunction "1_P$1") (pintype "passive"))
    )
    (net (code "124") (name "Net-(S37-1)") (class "Default")
      (node (ref "D37") (pin "A") (pinfunction "A_A") (pintype "passive"))
      (node (ref "S37") (pin "P$1") (pinfunction "1_P$1") (pintype "passive"))
    )
    (net (code "125") (name "Net-(S38-1)") (class "Default")
      (node (ref "D38") (pin "A") (pinfunction "A_A") (pintype "passive"))
      (node (ref "S38") (pin "P$1") (pinfunction "1_P$1") (pintype "passive"))
    )
    (net (code "126") (name "Net-(S39-1)") (class "Default")
      (node (ref "D39") (pin "A") (pinfunction "A_A") (pintype "passive"))
      (node (ref "S39") (pin "P$1") (pinfunction "1_P$1") (pintype "passive"))
    )
    (net (code "127") (name "Net-(S40-1)") (class "Default")
      (node (ref "D40") (pin "A") (pinfunction "A_A") (pintype "passive"))
      (node (ref "S40") (pin "P$1") (pinfunction "1_P$1") (pintype "passive"))
    )
    (net (code "128") (name "Net-(S41-1)") (class "Default")
      (node (ref "D41") (pin "A") (pinfunction "A_A") (pintype "passive"))
      (node (ref "S41") (pin "P$1") (pinfunction "1_P$1") (pintype "passive"))
    )
    (net (code "129") (name "Net-(S42-1)") (class "Default")
      (node (ref "D42") (pin "A") (pinfunction "A_A") (pintype "passive"))
      (node (ref "S42") (pin "P$1") (pinfunction "1_P$1") (pintype "passive"))
    )
    (net (code "130") (name "Net-(S43-1)") (class "Default")
      (node (ref "D43") (pin "A") (pinfunction "A_A") (pintype "passive"))
      (node (ref "S43") (pin "P$1") (pinfunction "1_P$1") (pintype "passive"))
    )
    (net (code "131") (name "Net-(S44-1)") (class "Default")
      (node (ref "D44") (pin "A") (pinfunction "A_A") (pintype "passive"))
      (node (ref "S44") (pin "P$1") (pinfunction "1_P$1") (pintype "passive"))
    )
    (net (code "132") (name "Net-(S45-1)") (class "Default")
      (node (ref "D45") (pin "A") (pinfunction "A_A") (pintype "passive"))
      (node (ref "S45") (pin "P$1") (pinfunction "1_P$1") (pintype "passive"))
    )
    (net (code "133") (name "Net-(S46-1)") (class "Default")
      (node (ref "D46") (pin "A") (pinfunction "A_A") (pintype "passive"))
      (node (ref "S46") (pin "P$1") (pinfunction "1_P$1") (pintype "passive"))
    )
    (net (code "134") (name "Net-(S47-1)") (class "Default")
      (node (ref "D47") (pin "A") (pinfunction "A_A") (pintype "passive"))
      (node (ref "S47") (pin "P$1") (pinfunction "1_P$1") (pintype "passive"))
    )
    (net (code "135") (name "Net-(S48-1)") (class "Default")
      (node (ref "D48") (pin "A") (pinfunction "A_A") (pintype "passive"))
      (node (ref "S48") (pin "P$1") (pinfunction "1_P$1") (pintype "passive"))
    )
    (net (code "136") (name "Net-(S49-1)") (class "Default")
      (node (ref "D49") (pin "A") (pinfunction "A_A") (pintype "passive"))
      (node (ref "S49") (pin "P$1") (pinfunction "1_P$1") (pintype "passive"))
    )
    (net (code "137") (name "Net-(S50-1)") (class "Default")
      (node (ref "D50") (pin "A") (pinfunction "A_A") (pintype "passive"))
      (node (ref "S50") (pin "P$1") (pinfunction "1_P$1") (pintype "passive"))
    )
    (net (code "138") (name "Net-(S51-1)") (class "Default")
      (node (ref "D51") (pin "A") (pinfunction "A_A") (pintype "passive"))
      (node (ref "S51") (pin "P$1") (pinfunction "1_P$1") (pintype "passive"))
    )
    (net (code "139") (name "Net-(S52-1)") (class "Default")
      (node (ref "D52") (pin "A") (pinfunction "A_A") (pintype "passive"))
      (node (ref "S52") (pin "P$1") (pinfunction "1_P$1") (pintype "passive"))
    )
    (net (code "140") (name "Net-(S53-1)") (class "Default")
      (node (ref "D53") (pin "A") (pinfunction "A_A") (pintype "passive"))
      (node (ref "S53") (pin "P$1") (pinfunction "1_P$1") (pintype "passive"))
    )
    (net (code "141") (name "Net-(S54-1)") (class "Default")
      (node (ref "D54") (pin "A") (pinfunction "A_A") (pintype "passive"))
      (node (ref "S54") (pin "P$1") (pinfunction "1_P$1") (pintype "passive"))
    )
    (net (code "142") (name "Net-(U1-USB_DM)") (class "Default")
      (node (ref "R2") (pin "1") (pinfunction "1_1") (pintype "passive"))
      (node (ref "U1") (pin "46") (pinfunction "USB_DM_46") (pintype "bidirectional"))
    )
    (net (code "143") (name "Net-(U1-USB_DP)") (class "Default")
      (node (ref "R3") (pin "2") (pinfunction "2_2") (pintype "passive"))
      (node (ref "U1") (pin "47") (pinfunction "USB_DP_47") (pintype "bidirectional"))
    )
    (net (code "144") (name "Net-(U3-~{CS})") (class "Default")
      (node (ref "R4") (pin "1") (pinfunction "1_1") (pintype "passive"))
      (node (ref "R6") (pin "2") (pinfunction "2_2") (pintype "passive"))
      (node (ref "U3") (pin "1") (pinfunction "~{CS}_1") (pintype "input"))
    )
    (net (code "145") (name "Net-(U4-Y)") (class "Default")
      (node (ref "R10") (pin "1") (pinfunction "1_1") (pintype "passive"))
      (node (ref "U4") (pin "4") (pinfunction "Y_4") (pintype "output"))
    )
    (net (code "146") (name "OLED_CS") (class "Default")
      (node (ref "J3") (pin "9") (pinfunction "9_9") (pintype "passive"))
      (node (ref "U1") (pin "34") (pinfunction "GPIO22_34") (pintype "bidirectional"))
    )
    (net (code "147") (name "OLED_DC") (class "Default")
      (node (ref "J3") (pin "7") (pinfunction "7_7") (pintype "passive"))
      (node (ref "U1") (pin "35") (pinfunction "GPIO23_35") (pintype "bidirectional"))
    )
    (net (code "148") (name "OLED_RST") (class "Default")
      (node (ref "J3") (pin "8") (pinfunction "8_8") (pintype "passive"))
      (node (ref "R8") (pin "2") (pinfunction "2_2") (pintype "passive"))
      (node (ref "U1") (pin "36") (pinfunction "GPIO24_36") (pintype "bidirectional"))
    )
    (net (code "149") (name "PMIC_ENABLE") (class "Default")
      (node (ref "J2") (pin "B4") (pinfunction "B4_B4") (pintype "passive"))
      (node (ref "S58") (pin "2") (pinfunction "2_2") (pintype "passive"))
    )
    (net (code "150") (name "PWR_BUTTON") (class "Default")
      (node (ref "J1") (pin "B3") (pinfunction "B3_B3") (pintype "passive"))
      (node (ref "S61") (pin "1") (pinfunction "1_1") (pintype "passive"))
      (node (ref "S61") (pin "2") (pinfunction "1_2") (pintype "passive"))
    )
    (net (code "151") (name "QSPI_SCLK") (class "Default")
      (node (ref "U1") (pin "52") (pinfunction "QSPI_SCLK_52") (pintype "bidirectional"))
      (node (ref "U3") (pin "6") (pinfunction "CLK_6") (pintype "input"))
    )
    (net (code "152") (name "QSPI_SD0") (class "Default")
      (node (ref "U1") (pin "53") (pinfunction "QSPI_SD0_53") (pintype "bidirectional"))
      (node (ref "U3") (pin "5") (pinfunction "DI(IO0)_5") (pintype "bidirectional"))
    )
    (net (code "153") (name "QSPI_SD1") (class "Default")
      (node (ref "U1") (pin "55") (pinfunction "QSPI_SD1_55") (pintype "bidirectional"))
      (node (ref "U3") (pin "2") (pinfunction "DO(IO1)_2") (pintype "bidirectional"))
    )
    (net (code "154") (name "QSPI_SD2") (class "Default")
      (node (ref "U1") (pin "54") (pinfunction "QSPI_SD2_54") (pintype "bidirectional"))
      (node (ref "U3") (pin "3") (pinfunction "~{WP}(IO2)_3") (pintype "bidirectional"))
    )
    (net (code "155") (name "QSPI_SD3") (class "Default")
      (node (ref "U1") (pin "51") (pinfunction "QSPI_SD3_51") (pintype "bidirectional"))
      (node (ref "U3") (pin "7") (pinfunction "~{HOLD}/~{RESET}/IO3_7") (pintype "bidirectional"))
    )
    (net (code "156") (name "RGB") (class "Default")
      (node (ref "R11") (pin "2") (pinfunction "2_2") (pintype "passive"))
      (node (ref "U1") (pin "28") (pinfunction "GPIO17_28") (pintype "bidirectional"))
      (node (ref "U5") (pin "2") (pinfunction "A_2") (pintype "input"))
    )
    (net (code "157") (name "RGB_5V") (class "Default")
      (node (ref "LED1") (pin "4") (pinfunction "DIN_4") (pintype "input"))
      (node (ref "U5") (pin "4") (pinfunction "Y_4") (pintype "output"))
    )
    (net (code "158") (name "ROT_A") (class "Default")
      (node (ref "R13") (pin "1") (pinfunction "1_1") (pintype "passive"))
      (node (ref "U$1") (pin "P$3") (pinfunction "A_P$3") (pintype "passive"))
      (node (ref "U1") (pin "29") (pinfunction "GPIO18_29") (pintype "bidirectional"))
    )
    (net (code "159") (name "ROT_B") (class "Default")
      (node (ref "R12") (pin "1") (pinfunction "1_1") (pintype "passive"))
      (node (ref "U$1") (pin "P$1") (pinfunction "B_P$1") (pintype "passive"))
      (node (ref "U1") (pin "30") (pinfunction "GPIO19_30") (pintype "bidirectional"))
    )
    (net (code "160") (name "ROT_S1") (class "Default")
      (node (ref "JP3") (pin "2") (pinfunction "2_2") (pintype "passive"))
      (node (ref "U$1") (pin "P$4") (pinfunction "S1_P$4") (pintype "passive"))
    )
    (net (code "161") (name "ROT_S2") (class "Default")
      (node (ref "D55") (pin "A") (pinfunction "A_A") (pintype "passive"))
      (node (ref "U$1") (pin "P$5") (pinfunction "S2_P$5") (pintype "passive"))
    )
    (net (code "162") (name "ROW0") (class "Default")
      (node (ref "D1") (pin "C") (pinfunction "K_C") (pintype "passive"))
      (node (ref "D10") (pin "C") (pinfunction "K_C") (pintype "passive"))
      (node (ref "D11") (pin "C") (pinfunction "K_C") (pintype "passive"))
      (node (ref "D12") (pin "C") (pinfunction "K_C") (pintype "passive"))
      (node (ref "D2") (pin "C") (pinfunction "K_C") (pintype "passive"))
      (node (ref "D3") (pin "C") (pinfunction "K_C") (pintype "passive"))
      (node (ref "D4") (pin "C") (pinfunction "K_C") (pintype "passive"))
      (node (ref "D5") (pin "C") (pinfunction "K_C") (pintype "passive"))
      (node (ref "D6") (pin "C") (pinfunction "K_C") (pintype "passive"))
      (node (ref "D7") (pin "C") (pinfunction "K_C") (pintype "passive"))
      (node (ref "D8") (pin "C") (pinfunction "K_C") (pintype "passive"))
      (node (ref "D9") (pin "C") (pinfunction "K_C") (pintype "passive"))
      (node (ref "U1") (pin "15") (pinfunction "GPIO12_15") (pintype "bidirectional"))
    )
    (net (code "163") (name "ROW1") (class "Default")
      (node (ref "D13") (pin "C") (pinfunction "K_C") (pintype "passive"))
      (node (ref "D14") (pin "C") (pinfunction "K_C") (pintype "passive"))
      (node (ref "D15") (pin "C") (pinfunction "K_C") (pintype "passive"))
      (node (ref "D16") (pin "C") (pinfunction "K_C") (pintype "passive"))
      (node (ref "D17") (pin "C") (pinfunction "K_C") (pintype "passive"))
      (node (ref "D18") (pin "C") (pinfunction "K_C") (pintype "passive"))
      (node (ref "D19") (pin "C") (pinfunction "K_C") (pintype "passive"))
      (node (ref "D20") (pin "C") (pinfunction "K_C") (pintype "passive"))
      (node (ref "D21") (pin "C") (pinfunction "K_C") (pintype "passive"))
      (node (ref "D22") (pin "C") (pinfunction "K_C") (pintype "passive"))
      (node (ref "D23") (pin "C") (pinfunction "K_C") (pintype "passive"))
      (node (ref "D24") (pin "C") (pinfunction "K_C") (pintype "passive"))
      (node (ref "U1") (pin "16") (pinfunction "GPIO13_16") (pintype "bidirectional"))
    )
    (net (code "164") (name "ROW2") (class "Default")
      (node (ref "D25") (pin "C") (pinfunction "K_C") (pintype "passive"))
      (node (ref "D26") (pin "C") (pinfunction "K_C") (pintype "passive"))
      (node (ref "D27") (pin "C") (pinfunction "K_C") (pintype "passive"))
      (node (ref "D28") (pin "C") (pinfunction "K_C") (pintype "passive"))
      (node (ref "D29") (pin "C") (pinfunction "K_C") (pintype "passive"))
      (node (ref "D30") (pin "C") (pinfunction "K_C") (pintype "passive"))
      (node (ref "D31") (pin "C") (pinfunction "K_C") (pintype "passive"))
      (node (ref "D32") (pin "C") (pinfunction "K_C") (pintype "passive"))
      (node (ref "D33") (pin "C") (pinfunction "K_C") (pintype "passive"))
      (node (ref "D34") (pin "C") (pinfunction "K_C") (pintype "passive"))
      (node (ref "D35") (pin "C") (pinfunction "K_C") (pintype "passive"))
      (node (ref "D36") (pin "C") (pinfunction "K_C") (pintype "passive"))
      (node (ref "U1") (pin "17") (pinfunction "GPIO14_17") (pintype "bidirectional"))
    )
    (net (code "165") (name "ROW3") (class "Default")
      (node (ref "D37") (pin "C") (pinfunction "K_C") (pintype "passive"))
      (node (ref "D38") (pin "C") (pinfunction "K_C") (pintype "passive"))
      (node (ref "D39") (pin "C") (pinfunction "K_C") (pintype "passive"))
      (node (ref "D40") (pin "C") (pinfunction "K_C") (pintype "passive"))
      (node (ref "D41") (pin "C") (pinfunction "K_C") (pintype "passive"))
      (node (ref "D42") (pin "C") (pinfunction "K_C") (pintype "passive"))
      (node (ref "D43") (pin "C") (pinfunction "K_C") (pintype "passive"))
      (node (ref "D44") (pin "C") (pinfunction "K_C") (pintype "passive"))
      (node (ref "D45") (pin "C") (pinfunction "K_C") (pintype "passive"))
      (node (ref "D46") (pin "C") (pinfunction "K_C") (pintype "passive"))
      (node (ref "D47") (pin "C") (pinfunction "K_C") (pintype "passive"))
      (node (ref "D48") (pin "C") (pinfunction "K_C") (pintype "passive"))
      (node (ref "U1") (pin "18") (pinfunction "GPIO15_18") (pintype "bidirectional"))
    )
    (net (code "166") (name "ROW4") (class "Default")
      (node (ref "D49") (pin "C") (pinfunction "K_C") (pintype "passive"))
      (node (ref "D50") (pin "C") (pinfunction "K_C") (pintype "passive"))
      (node (ref "D51") (pin "C") (pinfunction "K_C") (pintype "passive"))
      (node (ref "D52") (pin "C") (pinfunction "K_C") (pintype "passive"))
      (node (ref "D53") (pin "C") (pinfunction "K_C") (pintype "passive"))
      (node (ref "D54") (pin "C") (pinfunction "K_C") (pintype "passive"))
      (node (ref "D55") (pin "C") (pinfunction "K_C") (pintype "passive"))
      (node (ref "U1") (pin "27") (pinfunction "GPIO16_27") (pintype "bidirectional"))
    )
    (net (code "167") (name "SCK") (class "Default")
      (node (ref "J3") (pin "6") (pinfunction "6_6") (pintype "passive"))
      (node (ref "J4") (pin "12") (pinfunction "12_12") (pintype "passive"))
      (node (ref "U1") (pin "38") (pinfunction "GPIO26/ADC0_38") (pintype "bidirectional"))
    )
    (net (code "168") (name "SCL") (class "Default")
      (node (ref "J4") (pin "4") (pinfunction "4_4") (pintype "passive"))
      (node (ref "JP2") (pin "2") (pinfunction "2_2") (pintype "passive"))
      (node (ref "R14") (pin "1") (pinfunction "1_1") (pintype "passive"))
      (node (ref "TP10") (pin "TP") (pinfunction "TP_TP") (pintype "input"))
      (node (ref "U1") (pin "32") (pinfunction "GPIO21_32") (pintype "bidirectional"))
    )
    (net (code "169") (name "SDA") (class "Default")
      (node (ref "J4") (pin "3") (pinfunction "3_3") (pintype "passive"))
      (node (ref "JP1") (pin "2") (pinfunction "2_2") (pintype "passive"))
      (node (ref "R15") (pin "1") (pinfunction "1_1") (pintype "passive"))
      (node (ref "TP11") (pin "TP") (pinfunction "TP_TP") (pintype "input"))
      (node (ref "U1") (pin "31") (pinfunction "GPIO20_31") (pintype "bidirectional"))
    )
    (net (code "170") (name "SPK_L_N") (class "Default")
      (node (ref "J1") (pin "A2") (pinfunction "A2_A2") (pintype "passive"))
      (node (ref "LS1") (pin "N") (pinfunction "N_N") (pintype "passive"))
    )
    (net (code "171") (name "SPK_L_P") (class "Default")
      (node (ref "J1") (pin "A3") (pinfunction "A3_A3") (pintype "passive"))
      (node (ref "LS1") (pin "P") (pinfunction "P_P") (pintype "passive"))
    )
    (net (code "172") (name "SPK_R_N") (class "Default")
      (node (ref "J1") (pin "A5") (pinfunction "A5_A5") (pintype "passive"))
      (node (ref "LS2") (pin "N") (pinfunction "N_N") (pintype "passive"))
    )
    (net (code "173") (name "SPK_R_P") (class "Default")
      (node (ref "J1") (pin "A6") (pinfunction "A6_A6") (pintype "passive"))
      (node (ref "LS2") (pin "P") (pinfunction "P_P") (pintype "passive"))
    )
    (net (code "174") (name "SWCLK") (class "Default")
      (node (ref "TP2") (pin "TP") (pinfunction "TP_TP") (pintype "input"))
      (node (ref "U1") (pin "24") (pinfunction "SWCLK_24") (pintype "input"))
    )
    (net (code "175") (name "SWDIO") (class "Default")
      (node (ref "TP1") (pin "TP") (pinfunction "TP_TP") (pintype "input"))
      (node (ref "U1") (pin "25") (pinfunction "SWDIO_25") (pintype "bidirectional"))
    )
    (net (code "176") (name "TRACKPAD_CS") (class "Default")
      (node (ref "J4") (pin "10") (pinfunction "10_10") (pintype "passive"))
      (node (ref "U1") (pin "37") (pinfunction "GPIO25_37") (pintype "bidirectional"))
    )
    (net (code "177") (name "TRACKPAD_DR") (class "Default")
      (node (ref "J4") (pin "9") (pinfunction "9_9") (pintype "passive"))
      (node (ref "U1") (pin "41") (pinfunction "GPIO29/ADC3_41") (pintype "bidirectional"))
    )
    (net (code "178") (name "USB_N") (class "Default")
      (node (ref "J1") (pin "B5") (pinfunction "B5_B5") (pintype "passive"))
      (node (ref "R2") (pin "2") (pinfunction "2_2") (pintype "passive"))
      (node (ref "TP8") (pin "TP") (pinfunction "TP_TP") (pintype "input"))
    )
    (net (code "179") (name "USB_OTG_ID") (class "Default")
      (node (ref "J2") (pin "B5") (pinfunction "B5_B5") (pintype "passive"))
      (node (ref "S59") (pin "2") (pinfunction "2_2") (pintype "passive"))
    )
    (net (code "180") (name "USB_P") (class "Default")
      (node (ref "J1") (pin "B6") (pinfunction "B6_B6") (pintype "passive"))
      (node (ref "R3") (pin "1") (pinfunction "1_1") (pintype "passive"))
      (node (ref "TP9") (pin "TP") (pinfunction "TP_TP") (pintype "input"))
    )
    (net (code "181") (name "WL_~{DISABLE}") (class "Default")
      (node (ref "J2") (pin "B1") (pinfunction "B1_B1") (pintype "passive"))
      (node (ref "S55") (pin "2") (pinfunction "2_2") (pintype "passive"))
    )
    (net (code "182") (name "XIN") (class "Default")
      (node (ref "C14") (pin "2") (pinfunction "2_2") (pintype "passive"))
      (node (ref "U1") (pin "20") (pinfunction "XIN_20") (pintype "input"))
      (node (ref "Y1") (pin "1") (pinfunction "1_1") (pintype "passive"))
    )
    (net (code "183") (name "XOUT") (class "Default")
      (node (ref "R1") (pin "2") (pinfunction "2_2") (pintype "passive"))
      (node (ref "U1") (pin "21") (pinfunction "XOUT_21") (pintype "output"))
    )
    (net (code "184") (name "unconnected-(J4-Pad5)") (class "Default")
      (node (ref "J4") (pin "5") (pinfunction "5_5") (pintype "passive"))
    )
    (net (code "185") (name "unconnected-(J4-Pad6)") (class "Default")
      (node (ref "J4") (pin "6") (pinfunction "6_6") (pintype "passive"))
    )
    (net (code "186") (name "unconnected-(J4-Pad7)") (class "Default")
      (node (ref "J4") (pin "7") (pinfunction "7_7") (pintype "passive"))
    )
    (net (code "187") (name "unconnected-(LED54-DOUT-Pad2)") (class "Default")
      (node (ref "LED54") (pin "2") (pinfunction "DOUT_2") (pintype "output"))
    )
    (net (code "188") (name "unconnected-(S55-Pad3)") (class "Default")
      (node (ref "S55") (pin "3") (pinfunction "3_3") (pintype "passive"))
    )
    (net (code "189") (name "unconnected-(S56-Pad3)") (class "Default")
      (node (ref "S56") (pin "3") (pinfunction "3_3") (pintype "passive"))
    )
    (net (code "190") (name "unconnected-(S57-Pad1)") (class "Default")
      (node (ref "S57") (pin "1") (pinfunction "1_1") (pintype "passive"))
    )
    (net (code "191") (name "unconnected-(S58-Pad1)") (class "Default")
      (node (ref "S58") (pin "1") (pinfunction "1_1") (pintype "passive"))
    )
    (net (code "192") (name "unconnected-(S59-Pad1)") (class "Default")
      (node (ref "S59") (pin "1") (pinfunction "1_1") (pintype "passive"))
    )
    (net (code "193") (name "unconnected-(S60-Pad1)") (class "Default")
      (node (ref "S60") (pin "1") (pinfunction "1_1") (pintype "passive"))
    )
    (net (code "194") (name "unconnected-(U1-QSPI_SS_N-Pad56)") (class "Default")
      (node (ref "U1") (pin "56") (pinfunction "QSPI_SS_N_56") (pintype "bidirectional"))
    )
    (net (code "195") (name "unconnected-(U2-NC-Pad4)") (class "Default")
      (node (ref "U2") (pin "4") (pinfunction "NC_4") (pintype "passive"))
    )
    (net (code "196") (name "~{BOOT}") (class "Default")
      (node (ref "BOOT") (pin "1") (pinfunction "1_1") (pintype "passive"))
      (node (ref "BOOT") (pin "4") (pinfunction "1_4") (pintype "passive"))
      (node (ref "R6") (pin "1") (pinfunction "1_1") (pintype "passive"))
    )
    (net (code "197") (name "~{RESET}") (class "Default")
      (node (ref "R5") (pin "1") (pinfunction "1_1") (pintype "passive"))
      (node (ref "RESET") (pin "1") (pinfunction "1_1") (pintype "passive"))
      (node (ref "RESET") (pin "4") (pinfunction "1_4") (pintype "passive"))
      (node (ref "U1") (pin "26") (pinfunction "RUN_26") (pintype "input"))
    )
    (net (code "198") (name "~{RPIBOOT}") (class "Default")
      (node (ref "J2") (pin "B3") (pinfunction "B3_B3") (pintype "passive"))
      (node (ref "S57") (pin "2") (pinfunction "2_2") (pintype "passive"))
    )
  )
)
